# 28Pins_Schematic.net
KiCad netlist of a schematic drawn in Altium Designer
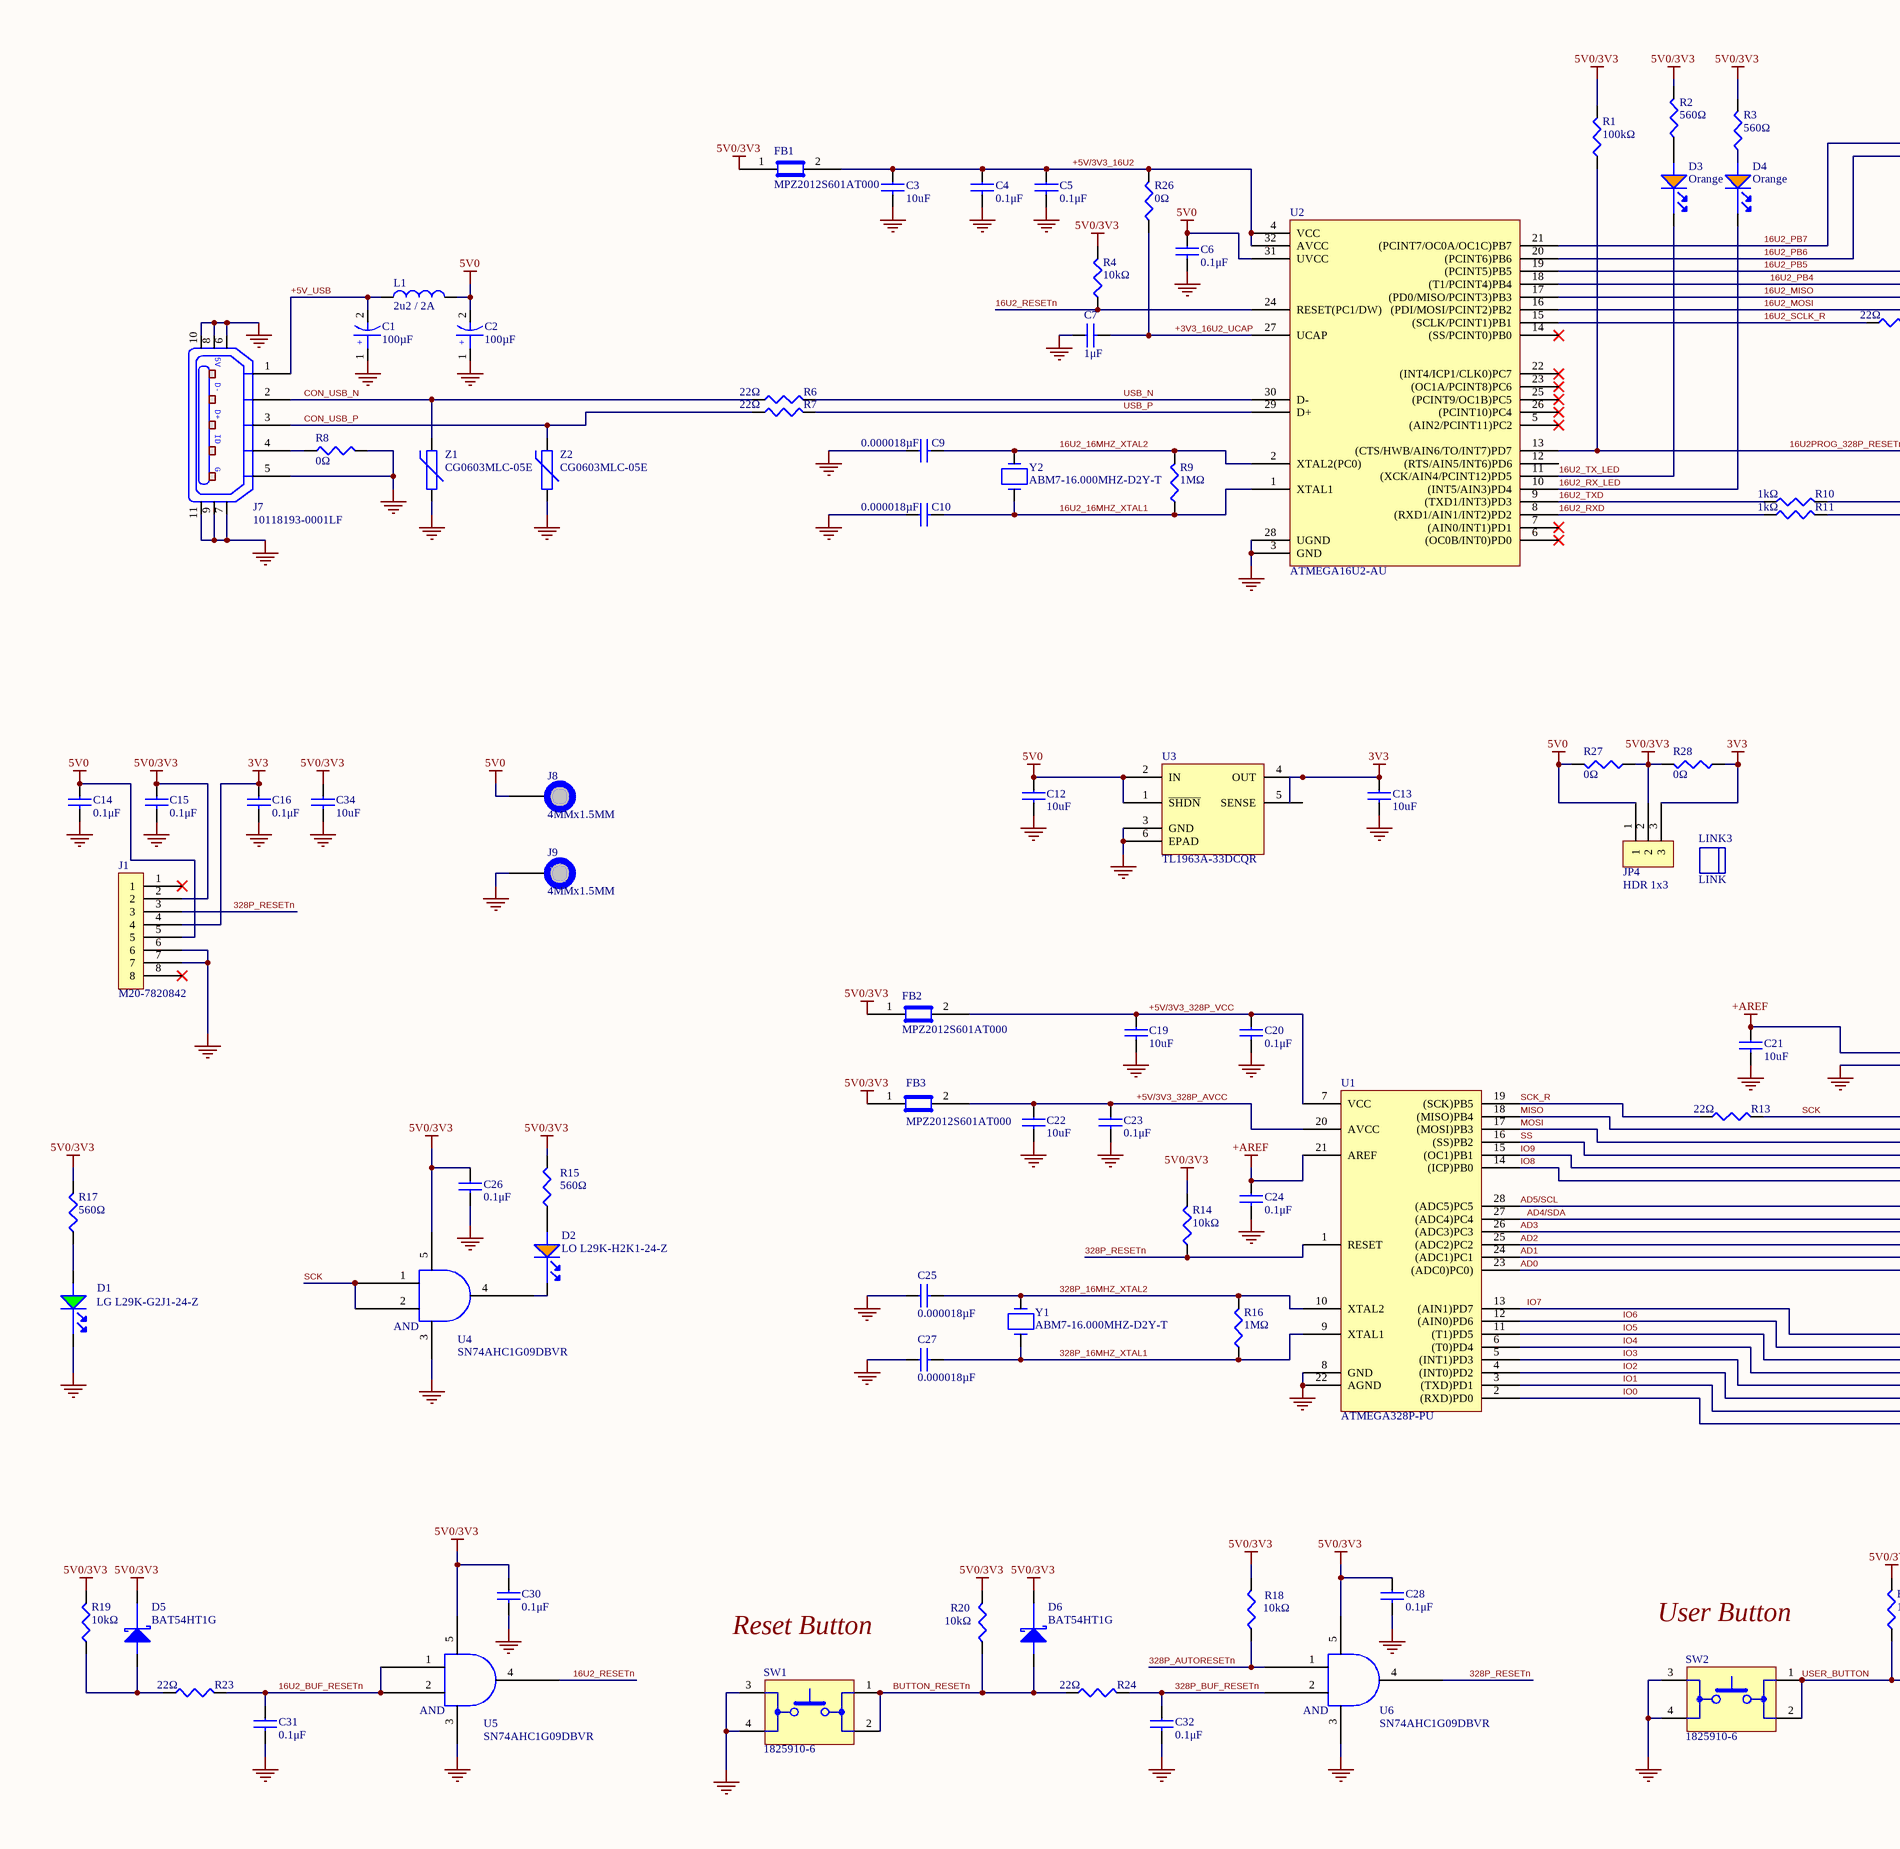
[diagram p0: 28Pins_Schematic.SchDoc, left]
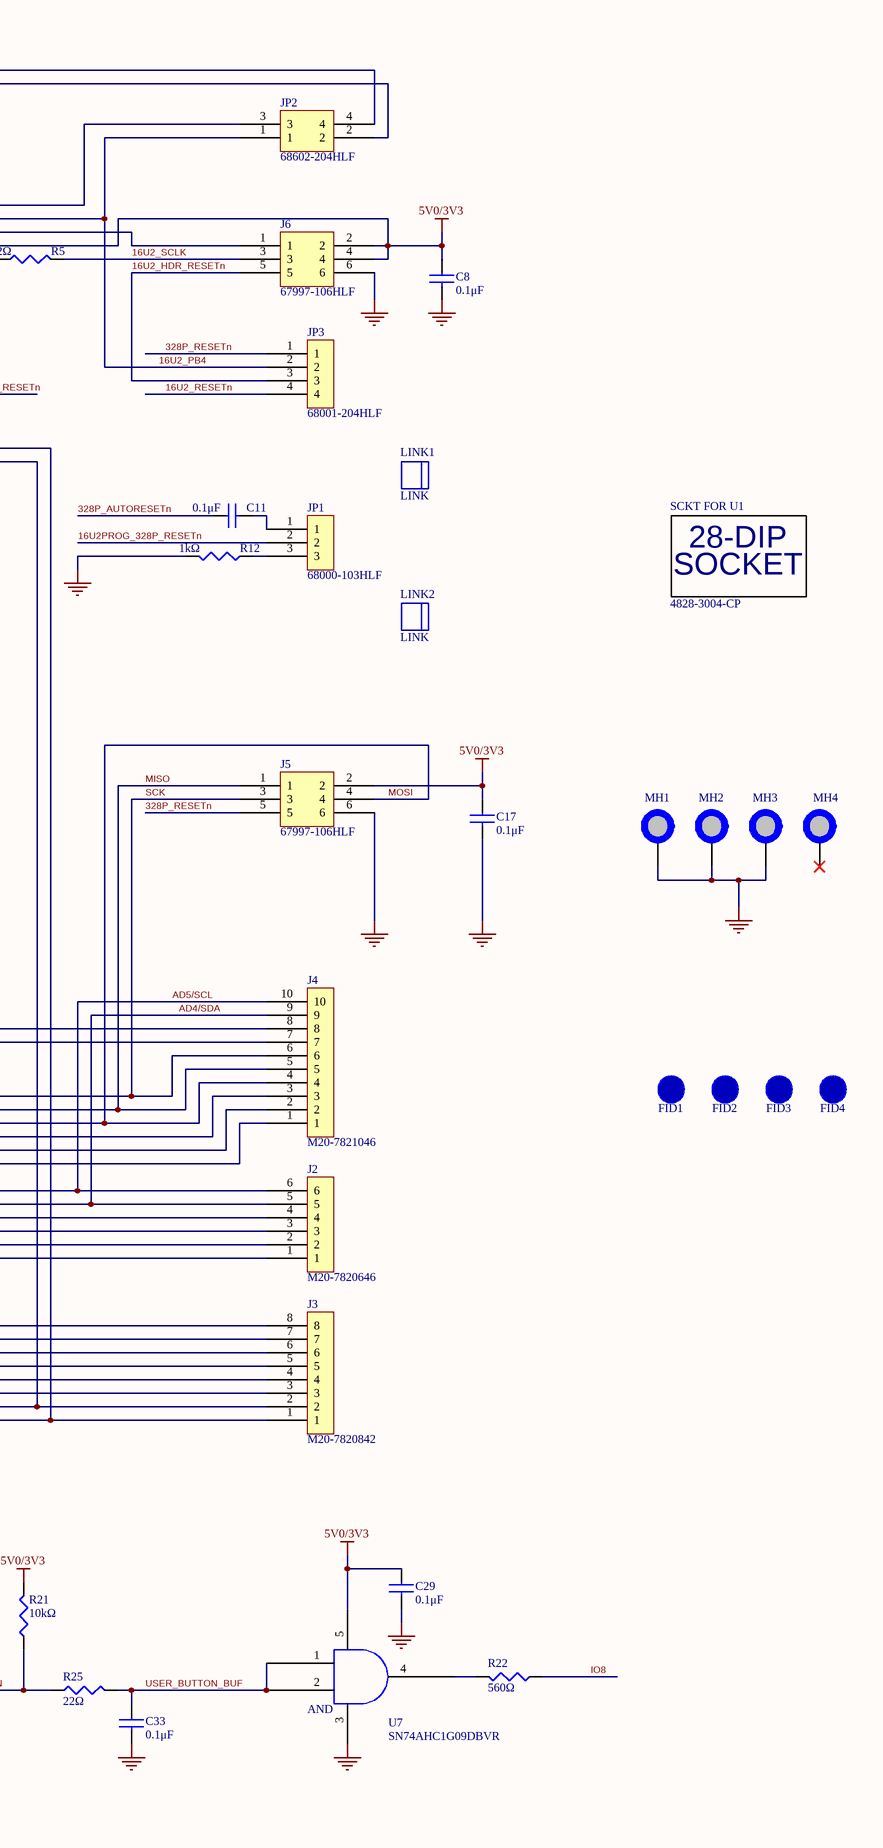
[diagram p1: 28Pins_Schematic.SchDoc, right]

(export (version "E")
  (design (tool "Eeschema 10.0.6"))
  (components
    (comp (ref "C1")
      (value "100µF")
      (footprint "C_ALU_C_SIZE")
      (description "CAP ALUM 100UF 10V 20% SMD")
      (fields
        (field (name "MANUFACTURER") "Panasonic Electronic Components")
        (field (name "MANUFACTURER PART NUMBER") "EEE-1AA101WR")
        (field (name ".CREATOR") "MM")
        (field (name ".CHECKED PCB") "RF")
        (field (name ".CHECKED SCH") "RF")
      )
      (libsource (lib "28Pins_Project_V1I1_PCB") (part "EEE-1AA101WR"))
    )
    (comp (ref "C2")
      (value "100µF")
      (footprint "C_ALU_C_SIZE")
      (description "CAP ALUM 100UF 10V 20% SMD")
      (fields
        (field (name "MANUFACTURER") "Panasonic Electronic Components")
        (field (name "MANUFACTURER PART NUMBER") "EEE-1AA101WR")
        (field (name ".CREATOR") "MM")
        (field (name ".CHECKED PCB") "RF")
        (field (name ".CHECKED SCH") "RF")
      )
      (libsource (lib "28Pins_Project_V1I1_PCB") (part "EEE-1AA101WR"))
    )
    (comp (ref "C3")
      (value "10uF")
      (footprint "C0805")
      (description "CAP CER 10UF 16V 20% X5R 0805")
      (fields
        (field (name "MANUFACTURER") "TDK Corporation")
        (field (name "MANUFACTURER PART NUMBER") "C2012X5R1C106M/1.25")
      )
      (libsource (lib "28Pins_Project_V1I1_PCB") (part "C2012X5R1C106M"))
    )
    (comp (ref "C4")
      (value "0.1μF")
      (footprint "C0805")
      (description "CAP CER 0.1UF 50V 10% X7R 0805")
      (fields
        (field (name "MANUFACTURER") "TDK Corporation")
        (field (name "MANUFACTURER PART NUMBER") "C2012X7R1H104K085AA")
        (field (name ".CREATOR") "MM")
        (field (name ".CHECKED PCB") "RF")
        (field (name ".CHECKED SCH") "RF")
      )
      (libsource (lib "28Pins_Project_V1I1_PCB") (part "C2012X7R1H104K085AA"))
    )
    (comp (ref "C5")
      (value "0.1μF")
      (footprint "C0805")
      (description "CAP CER 0.1UF 50V 10% X7R 0805")
      (fields
        (field (name "MANUFACTURER") "TDK Corporation")
        (field (name "MANUFACTURER PART NUMBER") "C2012X7R1H104K085AA")
        (field (name ".CREATOR") "MM")
        (field (name ".CHECKED PCB") "RF")
        (field (name ".CHECKED SCH") "RF")
      )
      (libsource (lib "28Pins_Project_V1I1_PCB") (part "C2012X7R1H104K085AA"))
    )
    (comp (ref "C6")
      (value "0.1μF")
      (footprint "C0805")
      (description "CAP CER 0.1UF 50V 10% X7R 0805")
      (fields
        (field (name "MANUFACTURER") "TDK Corporation")
        (field (name "MANUFACTURER PART NUMBER") "C2012X7R1H104K085AA")
        (field (name ".CREATOR") "MM")
        (field (name ".CHECKED PCB") "RF")
        (field (name ".CHECKED SCH") "RF")
      )
      (libsource (lib "28Pins_Project_V1I1_PCB") (part "C2012X7R1H104K085AA"))
    )
    (comp (ref "C7")
      (value "1μF")
      (footprint "C0805")
      (description "CAP CER 1UF 25V 10% X5R 0805")
      (fields
        (field (name "MANUFACTURER") "TDK Corporation")
        (field (name "MANUFACTURER PART NUMBER") "C2012X5R1E105K125AA")
        (field (name ".CREATOR") "MM")
        (field (name ".CHECKED PCB") "RF")
        (field (name ".CHECKED SCH") "RF")
      )
      (libsource (lib "28Pins_Project_V1I1_PCB") (part "C2012X5R1E105K125AA"))
    )
    (comp (ref "C8")
      (value "0.1μF")
      (footprint "C0805")
      (description "CAP CER 0.1UF 50V 10% X7R 0805")
      (fields
        (field (name "MANUFACTURER") "TDK Corporation")
        (field (name "MANUFACTURER PART NUMBER") "C2012X7R1H104K085AA")
        (field (name ".CREATOR") "MM")
        (field (name ".CHECKED PCB") "RF")
        (field (name ".CHECKED SCH") "RF")
      )
      (libsource (lib "28Pins_Project_V1I1_PCB") (part "C2012X7R1H104K085AA"))
    )
    (comp (ref "C9")
      (value "0.000018µF")
      (footprint "C0805")
      (description "CAP CER 18PF 50V 5% NP0 0805")
      (fields
        (field (name "MANUFACTURER") "Kemet")
        (field (name "MANUFACTURER PART NUMBER") "C0805C180J5GACTU")
        (field (name ".CREATOR") "MM")
        (field (name ".CHECKED PCB") "RF")
        (field (name ".CHECKED SCH") "RF")
      )
      (libsource (lib "28Pins_Project_V1I1_PCB") (part "C0805C180J5GACTU"))
    )
    (comp (ref "C10")
      (value "0.000018µF")
      (footprint "C0805")
      (description "CAP CER 18PF 50V 5% NP0 0805")
      (fields
        (field (name "MANUFACTURER") "Kemet")
        (field (name "MANUFACTURER PART NUMBER") "C0805C180J5GACTU")
        (field (name ".CREATOR") "MM")
        (field (name ".CHECKED PCB") "RF")
        (field (name ".CHECKED SCH") "RF")
      )
      (libsource (lib "28Pins_Project_V1I1_PCB") (part "C0805C180J5GACTU"))
    )
    (comp (ref "C11")
      (value "0.1μF")
      (footprint "C0805")
      (description "CAP CER 0.1UF 50V 10% X7R 0805")
      (fields
        (field (name "MANUFACTURER") "TDK Corporation")
        (field (name "MANUFACTURER PART NUMBER") "C2012X7R1H104K085AA")
        (field (name ".CREATOR") "MM")
        (field (name ".CHECKED PCB") "RF")
        (field (name ".CHECKED SCH") "RF")
      )
      (libsource (lib "28Pins_Project_V1I1_PCB") (part "C2012X7R1H104K085AA"))
    )
    (comp (ref "C12")
      (value "10uF")
      (footprint "C0805")
      (description "CAP CER 10UF 16V 20% X5R 0805")
      (fields
        (field (name "MANUFACTURER") "TDK Corporation")
        (field (name "MANUFACTURER PART NUMBER") "C2012X5R1C106M/1.25")
      )
      (libsource (lib "28Pins_Project_V1I1_PCB") (part "C2012X5R1C106M"))
    )
    (comp (ref "C13")
      (value "10uF")
      (footprint "C0805")
      (description "CAP CER 10UF 16V 20% X5R 0805")
      (fields
        (field (name "MANUFACTURER") "TDK Corporation")
        (field (name "MANUFACTURER PART NUMBER") "C2012X5R1C106M/1.25")
      )
      (libsource (lib "28Pins_Project_V1I1_PCB") (part "C2012X5R1C106M"))
    )
    (comp (ref "C14")
      (value "0.1μF")
      (footprint "C0805")
      (description "CAP CER 0.1UF 50V 10% X7R 0805")
      (fields
        (field (name "MANUFACTURER") "TDK Corporation")
        (field (name "MANUFACTURER PART NUMBER") "C2012X7R1H104K085AA")
        (field (name ".CREATOR") "MM")
        (field (name ".CHECKED PCB") "RF")
        (field (name ".CHECKED SCH") "RF")
      )
      (libsource (lib "28Pins_Project_V1I1_PCB") (part "C2012X7R1H104K085AA"))
    )
    (comp (ref "C15")
      (value "0.1μF")
      (footprint "C0805")
      (description "CAP CER 0.1UF 50V 10% X7R 0805")
      (fields
        (field (name "MANUFACTURER") "TDK Corporation")
        (field (name "MANUFACTURER PART NUMBER") "C2012X7R1H104K085AA")
        (field (name ".CREATOR") "MM")
        (field (name ".CHECKED PCB") "RF")
        (field (name ".CHECKED SCH") "RF")
      )
      (libsource (lib "28Pins_Project_V1I1_PCB") (part "C2012X7R1H104K085AA"))
    )
    (comp (ref "C16")
      (value "0.1μF")
      (footprint "C0805")
      (description "CAP CER 0.1UF 50V 10% X7R 0805")
      (fields
        (field (name "MANUFACTURER") "TDK Corporation")
        (field (name "MANUFACTURER PART NUMBER") "C2012X7R1H104K085AA")
        (field (name ".CREATOR") "MM")
        (field (name ".CHECKED PCB") "RF")
        (field (name ".CHECKED SCH") "RF")
      )
      (libsource (lib "28Pins_Project_V1I1_PCB") (part "C2012X7R1H104K085AA"))
    )
    (comp (ref "C17")
      (value "0.1μF")
      (footprint "C0805")
      (description "CAP CER 0.1UF 50V 10% X7R 0805")
      (fields
        (field (name "MANUFACTURER") "TDK Corporation")
        (field (name "MANUFACTURER PART NUMBER") "C2012X7R1H104K085AA")
        (field (name ".CREATOR") "MM")
        (field (name ".CHECKED PCB") "RF")
        (field (name ".CHECKED SCH") "RF")
      )
      (libsource (lib "28Pins_Project_V1I1_PCB") (part "C2012X7R1H104K085AA"))
    )
    (comp (ref "C19")
      (value "10uF")
      (footprint "C0805")
      (description "CAP CER 10UF 16V 20% X5R 0805")
      (fields
        (field (name "MANUFACTURER") "TDK Corporation")
        (field (name "MANUFACTURER PART NUMBER") "C2012X5R1C106M/1.25")
      )
      (libsource (lib "28Pins_Project_V1I1_PCB") (part "C2012X5R1C106M"))
    )
    (comp (ref "C20")
      (value "0.1μF")
      (footprint "C0805")
      (description "CAP CER 0.1UF 50V 10% X7R 0805")
      (fields
        (field (name "MANUFACTURER") "TDK Corporation")
        (field (name "MANUFACTURER PART NUMBER") "C2012X7R1H104K085AA")
        (field (name ".CREATOR") "MM")
        (field (name ".CHECKED PCB") "RF")
        (field (name ".CHECKED SCH") "RF")
      )
      (libsource (lib "28Pins_Project_V1I1_PCB") (part "C2012X7R1H104K085AA"))
    )
    (comp (ref "C21")
      (value "10uF")
      (footprint "C0805")
      (description "CAP CER 10UF 16V 20% X5R 0805")
      (fields
        (field (name "MANUFACTURER") "TDK Corporation")
        (field (name "MANUFACTURER PART NUMBER") "C2012X5R1C106M/1.25")
      )
      (libsource (lib "28Pins_Project_V1I1_PCB") (part "C2012X5R1C106M"))
    )
    (comp (ref "C22")
      (value "10uF")
      (footprint "C0805")
      (description "CAP CER 10UF 16V 20% X5R 0805")
      (fields
        (field (name "MANUFACTURER") "TDK Corporation")
        (field (name "MANUFACTURER PART NUMBER") "C2012X5R1C106M/1.25")
      )
      (libsource (lib "28Pins_Project_V1I1_PCB") (part "C2012X5R1C106M"))
    )
    (comp (ref "C23")
      (value "0.1μF")
      (footprint "C0805")
      (description "CAP CER 0.1UF 50V 10% X7R 0805")
      (fields
        (field (name "MANUFACTURER") "TDK Corporation")
        (field (name "MANUFACTURER PART NUMBER") "C2012X7R1H104K085AA")
        (field (name ".CREATOR") "MM")
        (field (name ".CHECKED PCB") "RF")
        (field (name ".CHECKED SCH") "RF")
      )
      (libsource (lib "28Pins_Project_V1I1_PCB") (part "C2012X7R1H104K085AA"))
    )
    (comp (ref "C24")
      (value "0.1μF")
      (footprint "C0805")
      (description "CAP CER 0.1UF 50V 10% X7R 0805")
      (fields
        (field (name "MANUFACTURER") "TDK Corporation")
        (field (name "MANUFACTURER PART NUMBER") "C2012X7R1H104K085AA")
        (field (name ".CREATOR") "MM")
        (field (name ".CHECKED PCB") "RF")
        (field (name ".CHECKED SCH") "RF")
      )
      (libsource (lib "28Pins_Project_V1I1_PCB") (part "C2012X7R1H104K085AA"))
    )
    (comp (ref "C25")
      (value "0.000018µF")
      (footprint "C0805")
      (description "CAP CER 18PF 50V 5% NP0 0805")
      (fields
        (field (name "MANUFACTURER") "Kemet")
        (field (name "MANUFACTURER PART NUMBER") "C0805C180J5GACTU")
        (field (name ".CREATOR") "MM")
        (field (name ".CHECKED PCB") "RF")
        (field (name ".CHECKED SCH") "RF")
      )
      (libsource (lib "28Pins_Project_V1I1_PCB") (part "C0805C180J5GACTU"))
    )
    (comp (ref "C26")
      (value "0.1μF")
      (footprint "C0805")
      (description "CAP CER 0.1UF 50V 10% X7R 0805")
      (fields
        (field (name "MANUFACTURER") "TDK Corporation")
        (field (name "MANUFACTURER PART NUMBER") "C2012X7R1H104K085AA")
        (field (name ".CREATOR") "MM")
        (field (name ".CHECKED PCB") "RF")
        (field (name ".CHECKED SCH") "RF")
      )
      (libsource (lib "28Pins_Project_V1I1_PCB") (part "C2012X7R1H104K085AA"))
    )
    (comp (ref "C27")
      (value "0.000018µF")
      (footprint "C0805")
      (description "CAP CER 18PF 50V 5% NP0 0805")
      (fields
        (field (name "MANUFACTURER") "Kemet")
        (field (name "MANUFACTURER PART NUMBER") "C0805C180J5GACTU")
        (field (name ".CREATOR") "MM")
        (field (name ".CHECKED PCB") "RF")
        (field (name ".CHECKED SCH") "RF")
      )
      (libsource (lib "28Pins_Project_V1I1_PCB") (part "C0805C180J5GACTU"))
    )
    (comp (ref "C28")
      (value "0.1μF")
      (footprint "C0805")
      (description "CAP CER 0.1UF 50V 10% X7R 0805")
      (fields
        (field (name "MANUFACTURER") "TDK Corporation")
        (field (name "MANUFACTURER PART NUMBER") "C2012X7R1H104K085AA")
        (field (name ".CREATOR") "MM")
        (field (name ".CHECKED PCB") "RF")
        (field (name ".CHECKED SCH") "RF")
      )
      (libsource (lib "28Pins_Project_V1I1_PCB") (part "C2012X7R1H104K085AA"))
    )
    (comp (ref "C29")
      (value "0.1μF")
      (footprint "C0805")
      (description "CAP CER 0.1UF 50V 10% X7R 0805")
      (fields
        (field (name "MANUFACTURER") "TDK Corporation")
        (field (name "MANUFACTURER PART NUMBER") "C2012X7R1H104K085AA")
        (field (name ".CREATOR") "MM")
        (field (name ".CHECKED PCB") "RF")
        (field (name ".CHECKED SCH") "RF")
      )
      (libsource (lib "28Pins_Project_V1I1_PCB") (part "C2012X7R1H104K085AA"))
    )
    (comp (ref "C30")
      (value "0.1μF")
      (footprint "C0805")
      (description "CAP CER 0.1UF 50V 10% X7R 0805")
      (fields
        (field (name "MANUFACTURER") "TDK Corporation")
        (field (name "MANUFACTURER PART NUMBER") "C2012X7R1H104K085AA")
        (field (name ".CREATOR") "MM")
        (field (name ".CHECKED PCB") "RF")
        (field (name ".CHECKED SCH") "RF")
      )
      (libsource (lib "28Pins_Project_V1I1_PCB") (part "C2012X7R1H104K085AA"))
    )
    (comp (ref "C31")
      (value "0.1μF")
      (footprint "C0805")
      (description "CAP CER 0.1UF 50V 10% X7R 0805")
      (fields
        (field (name "MANUFACTURER") "TDK Corporation")
        (field (name "MANUFACTURER PART NUMBER") "C2012X7R1H104K085AA")
        (field (name ".CREATOR") "MM")
        (field (name ".CHECKED PCB") "RF")
        (field (name ".CHECKED SCH") "RF")
      )
      (libsource (lib "28Pins_Project_V1I1_PCB") (part "C2012X7R1H104K085AA"))
    )
    (comp (ref "C32")
      (value "0.1μF")
      (footprint "C0805")
      (description "CAP CER 0.1UF 50V 10% X7R 0805")
      (fields
        (field (name "MANUFACTURER") "TDK Corporation")
        (field (name "MANUFACTURER PART NUMBER") "C2012X7R1H104K085AA")
        (field (name ".CREATOR") "MM")
        (field (name ".CHECKED PCB") "RF")
        (field (name ".CHECKED SCH") "RF")
      )
      (libsource (lib "28Pins_Project_V1I1_PCB") (part "C2012X7R1H104K085AA"))
    )
    (comp (ref "C33")
      (value "0.1μF")
      (footprint "C0805")
      (description "CAP CER 0.1UF 50V 10% X7R 0805")
      (fields
        (field (name "MANUFACTURER") "TDK Corporation")
        (field (name "MANUFACTURER PART NUMBER") "C2012X7R1H104K085AA")
        (field (name ".CREATOR") "MM")
        (field (name ".CHECKED PCB") "RF")
        (field (name ".CHECKED SCH") "RF")
      )
      (libsource (lib "28Pins_Project_V1I1_PCB") (part "C2012X7R1H104K085AA"))
    )
    (comp (ref "C34")
      (value "10uF")
      (footprint "C0805")
      (description "CAP CER 10UF 16V 20% X5R 0805")
      (fields
        (field (name "MANUFACTURER") "TDK Corporation")
        (field (name "MANUFACTURER PART NUMBER") "C2012X5R1C106M/1.25")
      )
      (libsource (lib "28Pins_Project_V1I1_PCB") (part "C2012X5R1C106M"))
    )
    (comp (ref "D1")
      (value "LG L29K-G2J1-24-Z")
      (footprint "LED_0603")
      (description "LED SMARTLED GREEN 570NM 0603")
      (fields (field (name "MANUFACTURER") "OSRAM Opto Semiconductors Inc"))
      (libsource (lib "28Pins_Project_V1I1_PCB") (part "LG L29K-G2J1-24-Z"))
    )
    (comp (ref "D2")
      (value "LO L29K-H2K1-24-Z")
      (footprint "LED_0603")
      (description "LED SMARTLED ORANGE 606NM 0603")
      (fields (field (name "MANUFACTURER") "OSRAM Opto Semiconductors Inc"))
      (libsource (lib "28Pins_Project_V1I1_PCB") (part "LO L29K-H2K1-24-Z"))
    )
    (comp (ref "D3")
      (value "Orange")
      (footprint "LED_0603")
      (description "LED SMARTLED ORANGE 606NM 0603")
      (fields
        (field (name "MANUFACTURER") "OSRAM Opto Semiconductors Inc")
        (field (name "MANUFACTURER PART NUMBER") "LO L29K-H2K1-24-Z")
      )
      (libsource (lib "28Pins_Project_V1I1_PCB") (part "LO L29K-H2K1-24-Z"))
    )
    (comp (ref "D4")
      (value "Orange")
      (footprint "LED_0603")
      (description "LED SMARTLED ORANGE 606NM 0603")
      (fields
        (field (name "MANUFACTURER") "OSRAM Opto Semiconductors Inc")
        (field (name "MANUFACTURER PART NUMBER") "LO L29K-H2K1-24-Z")
      )
      (libsource (lib "28Pins_Project_V1I1_PCB") (part "LO L29K-H2K1-24-Z"))
    )
    (comp (ref "D5")
      (value "BAT54HT1G")
      (footprint "SOD323")
      (description "DIODE SCHOTTKY 30V 0.2A SOD323")
      (fields (field (name "MANUFACTURER") "Fairchild Semiconductor") (field (name ".CREATOR") "MM"))
      (libsource (lib "28Pins_Project_V1I1_PCB") (part "BAT54HT1G"))
    )
    (comp (ref "D6")
      (value "BAT54HT1G")
      (footprint "SOD323")
      (description "DIODE SCHOTTKY 30V 0.2A SOD323")
      (fields (field (name "MANUFACTURER") "Fairchild Semiconductor") (field (name ".CREATOR") "MM"))
      (libsource (lib "28Pins_Project_V1I1_PCB") (part "BAT54HT1G"))
    )
    (comp (ref "FB1")
      (value "MPZ2012S601AT000")
      (footprint "C0805")
      (description "FERRITE CHIP BEAD 600 OHM SMD")
      (fields
        (field (name "MANUFACTURER") "TDK Corporation")
        (field (name ".CREATOR") "MM")
        (field (name ".CHECKED PCB") "RF")
        (field (name ".CHECKED SCH") "RF")
      )
      (libsource (lib "28Pins_Project_V1I1_PCB") (part "MPZ2012S601AT000"))
    )
    (comp (ref "FB2")
      (value "MPZ2012S601AT000")
      (footprint "C0805")
      (description "FERRITE CHIP BEAD 600 OHM SMD")
      (fields
        (field (name "MANUFACTURER") "TDK Corporation")
        (field (name ".CREATOR") "MM")
        (field (name ".CHECKED PCB") "RF")
        (field (name ".CHECKED SCH") "RF")
      )
      (libsource (lib "28Pins_Project_V1I1_PCB") (part "MPZ2012S601AT000"))
    )
    (comp (ref "FB3")
      (value "MPZ2012S601AT000")
      (footprint "C0805")
      (description "FERRITE CHIP BEAD 600 OHM SMD")
      (fields
        (field (name "MANUFACTURER") "TDK Corporation")
        (field (name ".CREATOR") "MM")
        (field (name ".CHECKED PCB") "RF")
        (field (name ".CHECKED SCH") "RF")
      )
      (libsource (lib "28Pins_Project_V1I1_PCB") (part "MPZ2012S601AT000"))
    )
    (comp (ref "FID1")
      (value "FID_1MMC")
      (footprint "FID_40X120D")
      (description "Fiducial 40mil Diameter, 120mil Mask")
      (libsource (lib "28Pins_Project_V1I1_PCB") (part "FID_1MMC"))
    )
    (comp (ref "FID2")
      (value "FID_1MMC")
      (footprint "FID_40X120D")
      (description "Fiducial 40mil Diameter, 120mil Mask")
      (libsource (lib "28Pins_Project_V1I1_PCB") (part "FID_1MMC"))
    )
    (comp (ref "FID3")
      (value "FID_1MMC")
      (footprint "FID_40X120D")
      (description "Fiducial 40mil Diameter, 120mil Mask")
      (libsource (lib "28Pins_Project_V1I1_PCB") (part "FID_1MMC"))
    )
    (comp (ref "FID4")
      (value "FID_1MMC")
      (footprint "FID_40X120D")
      (description "Fiducial 40mil Diameter, 120mil Mask")
      (libsource (lib "28Pins_Project_V1I1_PCB") (part "FID_1MMC"))
    )
    (comp (ref "J1")
      (value "M20-7820842")
      (footprint "Hdr_Female_1x8_2.54mm")
      (description "08-WAY SIL VERT SOCKET L/FREE")
      (fields
        (field (name "MANUFACTURER") "Harwin Inc")
        (field (name ".CREATOR") "MM")
        (field (name ".CHECKED PCB") "RF")
        (field (name ".CHECKED SCH") "RF")
      )
      (libsource (lib "") (part "M20-7820842_1"))
    )
    (comp (ref "J2")
      (value "M20-7820646")
      (footprint "Hdr_Female_1x6_2.54mm")
      (description "06-WAY SIL VERT SOCKET L/FREE")
      (fields
        (field (name "MANUFACTURER") "Harwin Inc")
        (field (name ".CHECKED PCB") "MM")
        (field (name ".CHECKED SCH") "MM")
        (field (name ".CREATOR") "MM")
      )
      (libsource (lib "28Pins_Project_V1I1_PCB") (part "M20-7820646"))
    )
    (comp (ref "J3")
      (value "M20-7820842")
      (footprint "Hdr_Female_1x8_2.54mm")
      (description "08-WAY SIL VERT SOCKET L/FREE")
      (fields
        (field (name "MANUFACTURER") "Harwin Inc")
        (field (name ".CREATOR") "MM")
        (field (name ".CHECKED PCB") "RF")
        (field (name ".CHECKED SCH") "RF")
      )
      (libsource (lib "28Pins_Project_V1I1_PCB") (part "M20-7820842"))
    )
    (comp (ref "J4")
      (value "M20-7821046")
      (footprint "Hdr_Female_1x10_2.54mm")
      (description "10-WAY SIL VERT SOCKET L/FREE")
      (fields
        (field (name "MANUFACTURER") "Harwin Inc")
        (field (name ".CREATOR") "MM")
        (field (name ".CHECKED PCB") "RF")
        (field (name ".CHECKED SCH") "RF")
      )
      (libsource (lib "28Pins_Project_V1I1_PCB") (part "M20-7821046"))
    )
    (comp (ref "J5")
      (value "67997-106HLF")
      (footprint "HDR_2x3_2.54MM")
      (description "CONN HEADER 6POS .100 STR 30AU")
      (fields
        (field (name "MANUFACTURER") "FCI")
        (field (name ".CREATOR") "MM")
        (field (name ".CHECKED PCB") "RF")
        (field (name ".CHECKED SCH") "RF")
      )
      (libsource (lib "28Pins_Project_V1I1_PCB") (part "67997-106HLF"))
    )
    (comp (ref "J6")
      (value "67997-106HLF")
      (footprint "HDR_2x3_2.54MM")
      (description "CONN HEADER 6POS .100 STR 30AU")
      (fields
        (field (name "MANUFACTURER") "FCI")
        (field (name ".CREATOR") "MM")
        (field (name ".CHECKED PCB") "RF")
        (field (name ".CHECKED SCH") "RF")
      )
      (libsource (lib "28Pins_Project_V1I1_PCB") (part "67997-106HLF"))
    )
    (comp (ref "J7")
      (value "10118193-0001LF")
      (footprint "10118193")
      (description "CONN USB MICRO B RECPT SMT R/A")
      (fields
        (field (name "MANUFACTURER") "FCI")
        (field (name ".CREATOR") "MM")
        (field (name ".CHECKED PCB") "RF")
        (field (name ".CHECKED SCH") "MM")
      )
      (libsource (lib "28Pins_Project_V1I1_PCB") (part "10118193-0001LF"))
    )
    (comp (ref "J8")
      (value "4MMx1.5MM")
      (footprint "PAD_WITH_HOLE_4MMx1.5MM")
      (description "Pad with a hole 4mm x 1.5mm")
      (libsource (lib "28Pins_Project_V1I1_PCB") (part "PAD_WITH_HOLE_4MMx1.5MM"))
    )
    (comp (ref "J9")
      (value "4MMx1.5MM")
      (footprint "PAD_WITH_HOLE_4MMx1.5MM")
      (description "Pad with a hole 4mm x 1.5mm")
      (libsource (lib "28Pins_Project_V1I1_PCB") (part "PAD_WITH_HOLE_4MMx1.5MM"))
    )
    (comp (ref "JP1")
      (value "68000-103HLF")
      (footprint "Hdr_1x3_2.54mm")
      (description "BERGSTIK II .100\" SR STRAIGHT")
      (fields (field (name "MANUFACTURER") "FCI") (field (name ".CREATOR") "MM"))
      (libsource (lib "28Pins_Project_V1I1_PCB") (part "68000-103HLF"))
    )
    (comp (ref "JP2")
      (value "68602-204HLF")
      (footprint "HDR_2x2_2.54MM")
      (description "CONN HEADER 4POS .100 STR 15AU")
      (fields
        (field (name "MANUFACTURER") "FCI")
        (field (name ".CREATOR") "MM")
        (field (name ".CHECKED PCB") "RF")
        (field (name ".CHECKED SCH") "RF")
      )
      (libsource (lib "28Pins_Project_V1I1_PCB") (part "68602-204HLF"))
    )
    (comp (ref "JP3")
      (value "68001-204HLF")
      (footprint "HDR_1x4_2.54MM")
      (description "CONN HEADER 4POS .100 STR 15AU")
      (fields
        (field (name "MANUFACTURER") "FCI")
        (field (name ".CHECKED PCB") "RF")
        (field (name ".CHECKED SCH") "RF")
      )
      (libsource (lib "28Pins_Project_V1I1_PCB") (part "68001-204HLF"))
    )
    (comp (ref "JP4")
      (value "HDR 1x3")
      (footprint "Hdr_1x3_2.54mm")
      (description "BERGSTIK II .100\" SR STRAIGHT")
      (fields
        (field (name "MANUFACTURER") "FCI")
        (field (name "MANUFACTURER PART NUMBER") "68000-103HLF")
        (field (name ".CREATOR") "MM")
      )
      (libsource (lib "") (part "68000-103HLF_1"))
    )
    (comp (ref "L1")
      (value "2u2 / 2A")
      (footprint "C1210_IND")
      (description "FIXED IND 2.2UH 2A 80 MOHM SMD")
      (fields
        (field (name "MANUFACTURER") "Kemet")
        (field (name "MANUFACTURER PART NUMBER") "L1210R2R2MDWIT")
        (field (name ".CREATOR") "MM")
        (field (name ".CHECKED PCB") "RF")
        (field (name ".CHECKED SCH") "RF")
      )
      (libsource (lib "28Pins_Project_V1I1_PCB") (part "L1210R2R2MDWIT"))
    )
    (comp (ref "LINK1")
      (value "LINK")
      (description "CONN JUMPER SHORTING .100\" GOLD")
      (fields
        (field (name "MANUFACTURER") "Sullins Connector Solutions")
        (field (name "MANUFACTURER PART NUMBER") "QPC02SXGN-RC")
      )
      (libsource (lib "28Pins_Project_V1I1_PCB") (part "QPC02SXGN-RC"))
    )
    (comp (ref "LINK2")
      (value "LINK")
      (description "CONN JUMPER SHORTING .100\" GOLD")
      (fields
        (field (name "MANUFACTURER") "Sullins Connector Solutions")
        (field (name "MANUFACTURER PART NUMBER") "QPC02SXGN-RC")
      )
      (libsource (lib "28Pins_Project_V1I1_PCB") (part "QPC02SXGN-RC"))
    )
    (comp (ref "LINK3")
      (value "LINK")
      (description "CONN JUMPER SHORTING .100\" GOLD")
      (fields
        (field (name "MANUFACTURER") "Sullins Connector Solutions")
        (field (name "MANUFACTURER PART NUMBER") "QPC02SXGN-RC")
      )
      (libsource (lib "28Pins_Project_V1I1_PCB") (part "QPC02SXGN-RC"))
    )
    (comp (ref "MH1")
      (value "MH_7.4MMC_3.2MMD")
      (footprint "MH_7.4MMD_3.2MMD")
      (description "Mounting Hole 7.4mm Diameter, 3.2mm Drill")
      (fields (field (name ".CREATOR") "MM"))
      (libsource (lib "28Pins_Project_V1I1_PCB") (part "MH_7.4MMC_3.2MMD"))
    )
    (comp (ref "MH2")
      (value "MH_7.4MMC_3.2MMD")
      (footprint "MH_7.4MMD_3.2MMD")
      (description "Mounting Hole 7.4mm Diameter, 3.2mm Drill")
      (fields (field (name ".CREATOR") "MM"))
      (libsource (lib "28Pins_Project_V1I1_PCB") (part "MH_7.4MMC_3.2MMD"))
    )
    (comp (ref "MH3")
      (value "MH_7.4MMC_3.2MMD")
      (footprint "MH_7.4MMD_3.2MMD")
      (description "Mounting Hole 7.4mm Diameter, 3.2mm Drill")
      (fields (field (name ".CREATOR") "MM"))
      (libsource (lib "28Pins_Project_V1I1_PCB") (part "MH_7.4MMC_3.2MMD"))
    )
    (comp (ref "MH4")
      (value "MH_7.4MMNC_3.2MMD")
      (footprint "MH_7.4MMD_3.2MMD_NON_COPPER_NPTH")
      (description "Mounting Hole 7.4mm Diameter (Non Copper), 3.2mm Drill NPTH")
      (libsource (lib "28Pins_Project_V1I1_PCB") (part "MH_7.4MMNC_3.2MMD"))
    )
    (comp (ref "R1")
      (value "100kΩ")
      (footprint "R0805")
      (description "RES SMD 100K OHM 1% 1/8W 0805")
      (fields
        (field (name "MANUFACTURER") "Yageo")
        (field (name "MANUFACTURER PART NUMBER") "RC0805FR-07100KL")
        (field (name ".CREATOR") "MM")
        (field (name ".CHECKED PCB") "RF")
        (field (name ".CHECKED SCH") "RF")
      )
      (libsource (lib "28Pins_Project_V1I1_PCB") (part "RC0805FR-07100KL"))
    )
    (comp (ref "R2")
      (value "560Ω")
      (footprint "R0805")
      (description "RES SMD 560 OHM 1% 1/8W 0805")
      (fields
        (field (name "MANUFACTURER") "Yageo")
        (field (name "MANUFACTURER PART NUMBER") "RC0805FR-07560RL")
        (field (name ".CREATOR") "MM")
        (field (name ".CHECKED PCB") "RF")
        (field (name ".CHECKED SCH") "RF")
      )
      (libsource (lib "28Pins_Project_V1I1_PCB") (part "RC0805FR-07560RL"))
    )
    (comp (ref "R3")
      (value "560Ω")
      (footprint "R0805")
      (description "RES SMD 560 OHM 1% 1/8W 0805")
      (fields
        (field (name "MANUFACTURER") "Yageo")
        (field (name "MANUFACTURER PART NUMBER") "RC0805FR-07560RL")
        (field (name ".CREATOR") "MM")
        (field (name ".CHECKED PCB") "RF")
        (field (name ".CHECKED SCH") "RF")
      )
      (libsource (lib "28Pins_Project_V1I1_PCB") (part "RC0805FR-07560RL"))
    )
    (comp (ref "R4")
      (value "10kΩ")
      (footprint "R0805")
      (description "RES SMD 10K OHM 1% 1/8W 0805")
      (fields
        (field (name "MANUFACTURER") "Yageo")
        (field (name "MANUFACTURER PART NUMBER") "RC0805FR-0710KL")
        (field (name ".CREATOR") "MM")
        (field (name ".CHECKED PCB") "RF")
        (field (name ".CHECKED SCH") "RF")
      )
      (libsource (lib "28Pins_Project_V1I1_PCB") (part "RC0805FR-0710KL"))
    )
    (comp (ref "R5")
      (value "22Ω")
      (footprint "R0805")
      (description "RES SMD 22 OHM 1% 1/8W 0805")
      (fields
        (field (name "MANUFACTURER") "Yageo")
        (field (name "MANUFACTURER PART NUMBER") "RC0805FR-0722RL")
        (field (name ".CREATOR") "MM")
        (field (name ".CHECKED PCB") "RF")
        (field (name ".CHECKED SCH") "RF")
      )
      (libsource (lib "28Pins_Project_V1I1_PCB") (part "RC0805FR-0722RL"))
    )
    (comp (ref "R6")
      (value "22Ω")
      (footprint "R0805")
      (description "RES SMD 22 OHM 1% 1/8W 0805")
      (fields
        (field (name "MANUFACTURER") "Yageo")
        (field (name "MANUFACTURER PART NUMBER") "RC0805FR-0722RL")
        (field (name ".CREATOR") "MM")
        (field (name ".CHECKED PCB") "RF")
        (field (name ".CHECKED SCH") "RF")
      )
      (libsource (lib "28Pins_Project_V1I1_PCB") (part "RC0805FR-0722RL"))
    )
    (comp (ref "R7")
      (value "22Ω")
      (footprint "R0805")
      (description "RES SMD 22 OHM 1% 1/8W 0805")
      (fields
        (field (name "MANUFACTURER") "Yageo")
        (field (name "MANUFACTURER PART NUMBER") "RC0805FR-0722RL")
        (field (name ".CREATOR") "MM")
        (field (name ".CHECKED PCB") "RF")
        (field (name ".CHECKED SCH") "RF")
      )
      (libsource (lib "28Pins_Project_V1I1_PCB") (part "RC0805FR-0722RL"))
    )
    (comp (ref "R8")
      (value "0Ω")
      (footprint "R0805")
      (description "RES 0.0 OHM 1/8W 0805 SMD")
      (fields
        (field (name "MANUFACTURER") "Yageo")
        (field (name "MANUFACTURER PART NUMBER") "RC0805JR-070RL")
        (field (name ".CHECKED PCB") "RF")
        (field (name ".CHECKED SCH") "RF")
      )
      (libsource (lib "28Pins_Project_V1I1_PCB") (part "RC0805JR-070RL"))
    )
    (comp (ref "R9")
      (value "1MΩ")
      (footprint "R0805")
      (description "RES SMD 1M OHM 1% 1/8W 0805")
      (fields
        (field (name "MANUFACTURER") "Yageo")
        (field (name "MANUFACTURER PART NUMBER") "RC0805FR-071ML")
        (field (name ".CREATOR") "MM")
        (field (name ".CHECKED PCB") "RF")
        (field (name ".CHECKED SCH") "RF")
      )
      (libsource (lib "28Pins_Project_V1I1_PCB") (part "RC0805FR-071ML"))
    )
    (comp (ref "R10")
      (value "1kΩ")
      (footprint "R0805")
      (description "RES SMD 1K OHM 1% 1/8W 0805")
      (fields
        (field (name "MANUFACTURER") "Yageo")
        (field (name "MANUFACTURER PART NUMBER") "RC0805FR-071KL")
        (field (name ".CREATOR") "MM")
        (field (name ".CHECKED PCB") "RF")
        (field (name ".CHECKED SCH") "RF")
      )
      (libsource (lib "28Pins_Project_V1I1_PCB") (part "RC0805FR-071KL"))
    )
    (comp (ref "R11")
      (value "1kΩ")
      (footprint "R0805")
      (description "RES SMD 1K OHM 1% 1/8W 0805")
      (fields
        (field (name "MANUFACTURER") "Yageo")
        (field (name "MANUFACTURER PART NUMBER") "RC0805FR-071KL")
        (field (name ".CREATOR") "MM")
        (field (name ".CHECKED PCB") "RF")
        (field (name ".CHECKED SCH") "RF")
      )
      (libsource (lib "28Pins_Project_V1I1_PCB") (part "RC0805FR-071KL"))
    )
    (comp (ref "R12")
      (value "1kΩ")
      (footprint "R0805")
      (description "RES SMD 1K OHM 1% 1/8W 0805")
      (fields
        (field (name "MANUFACTURER") "Yageo")
        (field (name "MANUFACTURER PART NUMBER") "RC0805FR-071KL")
        (field (name ".CREATOR") "MM")
        (field (name ".CHECKED PCB") "RF")
        (field (name ".CHECKED SCH") "RF")
      )
      (libsource (lib "28Pins_Project_V1I1_PCB") (part "RC0805FR-071KL"))
    )
    (comp (ref "R13")
      (value "22Ω")
      (footprint "R0805")
      (description "RES SMD 22 OHM 1% 1/8W 0805")
      (fields
        (field (name "MANUFACTURER") "Yageo")
        (field (name "MANUFACTURER PART NUMBER") "RC0805FR-0722RL")
        (field (name ".CREATOR") "MM")
        (field (name ".CHECKED PCB") "RF")
        (field (name ".CHECKED SCH") "RF")
      )
      (libsource (lib "28Pins_Project_V1I1_PCB") (part "RC0805FR-0722RL"))
    )
    (comp (ref "R14")
      (value "10kΩ")
      (footprint "R0805")
      (description "RES SMD 10K OHM 1% 1/8W 0805")
      (fields
        (field (name "MANUFACTURER") "Yageo")
        (field (name "MANUFACTURER PART NUMBER") "RC0805FR-0710KL")
        (field (name ".CREATOR") "MM")
        (field (name ".CHECKED PCB") "RF")
        (field (name ".CHECKED SCH") "RF")
      )
      (libsource (lib "28Pins_Project_V1I1_PCB") (part "RC0805FR-0710KL"))
    )
    (comp (ref "R15")
      (value "560Ω")
      (footprint "R0805")
      (description "RES SMD 560 OHM 1% 1/8W 0805")
      (fields
        (field (name "MANUFACTURER") "Yageo")
        (field (name "MANUFACTURER PART NUMBER") "RC0805FR-07560RL")
        (field (name ".CREATOR") "MM")
        (field (name ".CHECKED PCB") "RF")
        (field (name ".CHECKED SCH") "RF")
      )
      (libsource (lib "28Pins_Project_V1I1_PCB") (part "RC0805FR-07560RL"))
    )
    (comp (ref "R16")
      (value "1MΩ")
      (footprint "R0805")
      (description "RES SMD 1M OHM 1% 1/8W 0805")
      (fields
        (field (name "MANUFACTURER") "Yageo")
        (field (name "MANUFACTURER PART NUMBER") "RC0805FR-071ML")
        (field (name ".CREATOR") "MM")
        (field (name ".CHECKED PCB") "RF")
        (field (name ".CHECKED SCH") "RF")
      )
      (libsource (lib "28Pins_Project_V1I1_PCB") (part "RC0805FR-071ML"))
    )
    (comp (ref "R17")
      (value "560Ω")
      (footprint "R0805")
      (description "RES SMD 560 OHM 1% 1/8W 0805")
      (fields
        (field (name "MANUFACTURER") "Yageo")
        (field (name "MANUFACTURER PART NUMBER") "RC0805FR-07560RL")
        (field (name ".CREATOR") "MM")
        (field (name ".CHECKED PCB") "RF")
        (field (name ".CHECKED SCH") "RF")
      )
      (libsource (lib "28Pins_Project_V1I1_PCB") (part "RC0805FR-07560RL"))
    )
    (comp (ref "R18")
      (value "10kΩ")
      (footprint "R0805")
      (description "RES SMD 10K OHM 1% 1/8W 0805")
      (fields
        (field (name "MANUFACTURER") "Yageo")
        (field (name "MANUFACTURER PART NUMBER") "RC0805FR-0710KL")
        (field (name ".CREATOR") "MM")
        (field (name ".CHECKED PCB") "RF")
        (field (name ".CHECKED SCH") "RF")
      )
      (libsource (lib "28Pins_Project_V1I1_PCB") (part "RC0805FR-0710KL"))
    )
    (comp (ref "R19")
      (value "10kΩ")
      (footprint "R0805")
      (description "RES SMD 10K OHM 1% 1/8W 0805")
      (fields
        (field (name "MANUFACTURER") "Yageo")
        (field (name "MANUFACTURER PART NUMBER") "RC0805FR-0710KL")
        (field (name ".CREATOR") "MM")
        (field (name ".CHECKED PCB") "RF")
        (field (name ".CHECKED SCH") "RF")
      )
      (libsource (lib "28Pins_Project_V1I1_PCB") (part "RC0805FR-0710KL"))
    )
    (comp (ref "R20")
      (value "10kΩ")
      (footprint "R0805")
      (description "RES SMD 10K OHM 1% 1/8W 0805")
      (fields
        (field (name "MANUFACTURER") "Yageo")
        (field (name "MANUFACTURER PART NUMBER") "RC0805FR-0710KL")
        (field (name ".CREATOR") "MM")
        (field (name ".CHECKED PCB") "RF")
        (field (name ".CHECKED SCH") "RF")
      )
      (libsource (lib "28Pins_Project_V1I1_PCB") (part "RC0805FR-0710KL"))
    )
    (comp (ref "R21")
      (value "10kΩ")
      (footprint "R0805")
      (description "RES SMD 10K OHM 1% 1/8W 0805")
      (fields
        (field (name "MANUFACTURER") "Yageo")
        (field (name "MANUFACTURER PART NUMBER") "RC0805FR-0710KL")
        (field (name ".CREATOR") "MM")
        (field (name ".CHECKED PCB") "RF")
        (field (name ".CHECKED SCH") "RF")
      )
      (libsource (lib "28Pins_Project_V1I1_PCB") (part "RC0805FR-0710KL"))
    )
    (comp (ref "R22")
      (value "560Ω")
      (footprint "R0805")
      (description "RES SMD 560 OHM 1% 1/8W 0805")
      (fields
        (field (name "MANUFACTURER") "Yageo")
        (field (name "MANUFACTURER PART NUMBER") "RC0805FR-07560RL")
        (field (name ".CREATOR") "MM")
        (field (name ".CHECKED PCB") "RF")
        (field (name ".CHECKED SCH") "RF")
      )
      (libsource (lib "28Pins_Project_V1I1_PCB") (part "RC0805FR-07560RL"))
    )
    (comp (ref "R23")
      (value "22Ω")
      (footprint "R0805")
      (description "RES SMD 22 OHM 1% 1/8W 0805")
      (fields
        (field (name "MANUFACTURER") "Yageo")
        (field (name "MANUFACTURER PART NUMBER") "RC0805FR-0722RL")
        (field (name ".CREATOR") "MM")
        (field (name ".CHECKED PCB") "RF")
        (field (name ".CHECKED SCH") "RF")
      )
      (libsource (lib "28Pins_Project_V1I1_PCB") (part "RC0805FR-0722RL"))
    )
    (comp (ref "R24")
      (value "22Ω")
      (footprint "R0805")
      (description "RES SMD 22 OHM 1% 1/8W 0805")
      (fields
        (field (name "MANUFACTURER") "Yageo")
        (field (name "MANUFACTURER PART NUMBER") "RC0805FR-0722RL")
        (field (name ".CREATOR") "MM")
        (field (name ".CHECKED PCB") "RF")
        (field (name ".CHECKED SCH") "RF")
      )
      (libsource (lib "28Pins_Project_V1I1_PCB") (part "RC0805FR-0722RL"))
    )
    (comp (ref "R25")
      (value "22Ω")
      (footprint "R0805")
      (description "RES SMD 22 OHM 1% 1/8W 0805")
      (fields
        (field (name "MANUFACTURER") "Yageo")
        (field (name "MANUFACTURER PART NUMBER") "RC0805FR-0722RL")
        (field (name ".CREATOR") "MM")
        (field (name ".CHECKED PCB") "RF")
        (field (name ".CHECKED SCH") "RF")
      )
      (libsource (lib "28Pins_Project_V1I1_PCB") (part "RC0805FR-0722RL"))
    )
    (comp (ref "R26")
      (value "0Ω")
      (footprint "R0805")
      (description "RES 0.0 OHM 1/8W 0805 SMD")
      (fields
        (field (name "MANUFACTURER") "Yageo")
        (field (name "MANUFACTURER PART NUMBER") "RC0805JR-070RL")
        (field (name ".CHECKED PCB") "RF")
        (field (name ".CHECKED SCH") "RF")
      )
      (libsource (lib "28Pins_Project_V1I1_PCB") (part "RC0805JR-070RL"))
    )
    (comp (ref "R27")
      (value "0Ω")
      (footprint "R0805")
      (description "RES 0.0 OHM 1/8W 0805 SMD")
      (fields
        (field (name "MANUFACTURER") "Yageo")
        (field (name "MANUFACTURER PART NUMBER") "RC0805JR-070RL")
        (field (name ".CHECKED PCB") "RF")
        (field (name ".CHECKED SCH") "RF")
      )
      (libsource (lib "28Pins_Project_V1I1_PCB") (part "RC0805JR-070RL"))
    )
    (comp (ref "R28")
      (value "0Ω")
      (footprint "R0805")
      (description "RES 0.0 OHM 1/8W 0805 SMD")
      (fields
        (field (name "MANUFACTURER") "Yageo")
        (field (name "MANUFACTURER PART NUMBER") "RC0805JR-070RL")
        (field (name ".CHECKED PCB") "RF")
        (field (name ".CHECKED SCH") "RF")
      )
      (libsource (lib "28Pins_Project_V1I1_PCB") (part "RC0805JR-070RL"))
    )
    (comp (ref "SCKT FOR U1")
      (value "4828-3004-CP")
      (footprint "28_DIP_7.62mm_SOCKET")
      (description "CONN IC DIP SOCKET 28POS TIN")
      (fields
        (field (name "MANUFACTURER") "3M")
        (field (name ".CREATOR") "MM")
        (field (name ".CHECKED PCB") "RF")
        (field (name ".CHECKED SCH") "RF")
      )
      (libsource (lib "28Pins_Project_V1I1_PCB") (part "4828-3004-CP"))
    )
    (comp (ref "SW1")
      (value "1825910-6")
      (footprint "1825910-6")
      (description "SWITCH TACTILE SPST-NO 0.05A 24V")
      (fields
        (field (name "MANUFACTURER") "TE Connectivity")
        (field (name ".CREATOR") "MM")
        (field (name ".CHECKED PCB") "RF")
        (field (name ".CHECKED SCH") "RF")
      )
      (libsource (lib "28Pins_Project_V1I1_PCB") (part "1825910-6"))
    )
    (comp (ref "SW2")
      (value "1825910-6")
      (footprint "1825910-6")
      (description "SWITCH TACTILE SPST-NO 0.05A 24V")
      (fields
        (field (name "MANUFACTURER") "TE Connectivity")
        (field (name ".CREATOR") "MM")
        (field (name ".CHECKED PCB") "RF")
        (field (name ".CHECKED SCH") "RF")
      )
      (libsource (lib "28Pins_Project_V1I1_PCB") (part "1825910-6"))
    )
    (comp (ref "U1")
      (value "ATMEGA328P-PU")
      (footprint "28_DIP_7.62mm")
      (description "IC MCU 8BIT 32KB FLASH 28DIP")
      (fields
        (field (name "MANUFACTURER") "Atmel")
        (field (name ".CREATOR") "MM")
        (field (name ".CHECKED PCB") "RF")
        (field (name ".CHECKED SCH") "RF")
      )
      (libsource (lib "28Pins_Project_V1I1_PCB") (part "ATMEGA328P-PU"))
    )
    (comp (ref "U2")
      (value "ATMEGA16U2-AU")
      (footprint "TQFP32")
      (description "IC MCU 8BIT 16KB FLASH 32TQFP")
      (fields
        (field (name "MANUFACTURER") "Atmel")
        (field (name ".CREATOR") "MM")
        (field (name ".CHECKED PCB") "RF")
        (field (name ".CHECKED SCH") "RF")
      )
      (libsource (lib "28Pins_Project_V1I1_PCB") (part "ATMEGA16U2-AU"))
    )
    (comp (ref "U3")
      (value "TL1963A-33DCQR")
      (footprint "DCQ (R-PDSO-G6)")
      (description "IC REG LDO 3.3V 1.5A SOT223-6")
      (fields
        (field (name "MANUFACTURER") "Texas Instruments")
        (field (name ".CREATOR") "MM")
        (field (name ".CHECKED PCB") "RF")
        (field (name ".CHECKED SCH") "RF")
      )
      (libsource (lib "28Pins_Project_V1I1_PCB") (part "TL1963A-33DCQR"))
    )
    (comp (ref "U4")
      (value "SN74AHC1G09DBVR")
      (footprint "DBV_SOT_23_5")
      (description "IC GATE AND SGL 2INP SOT23-5")
      (fields (field (name "MANUFACTURER") "Texas Instruments") (field (name ".CREATOR") "MM"))
      (libsource (lib "28Pins_Project_V1I1_PCB") (part "SN74AHC1G09DBVR"))
    )
    (comp (ref "U5")
      (value "SN74AHC1G09DBVR")
      (footprint "DBV_SOT_23_5")
      (description "IC GATE AND SGL 2INP SOT23-5")
      (fields (field (name "MANUFACTURER") "Texas Instruments") (field (name ".CREATOR") "MM"))
      (libsource (lib "28Pins_Project_V1I1_PCB") (part "SN74AHC1G09DBVR"))
    )
    (comp (ref "U6")
      (value "SN74AHC1G09DBVR")
      (footprint "DBV_SOT_23_5")
      (description "IC GATE AND SGL 2INP SOT23-5")
      (fields (field (name "MANUFACTURER") "Texas Instruments") (field (name ".CREATOR") "MM"))
      (libsource (lib "28Pins_Project_V1I1_PCB") (part "SN74AHC1G09DBVR"))
    )
    (comp (ref "U7")
      (value "SN74AHC1G09DBVR")
      (footprint "DBV_SOT_23_5")
      (description "IC GATE AND SGL 2INP SOT23-5")
      (fields (field (name "MANUFACTURER") "Texas Instruments") (field (name ".CREATOR") "MM"))
      (libsource (lib "28Pins_Project_V1I1_PCB") (part "SN74AHC1G09DBVR"))
    )
    (comp (ref "Y1")
      (value "ABM7-16.000MHZ-D2Y-T")
      (footprint "ABM7_v1_1_BIG")
      (description "CRYSTAL 16MHZ 18PF SMD")
      (fields
        (field (name "MANUFACTURER") "Abracon LLC")
        (field (name ".CREATOR") "MM")
        (field (name ".CHECKED PCB") "RF")
        (field (name ".CHECKED SCH") "RF")
      )
      (libsource (lib "28Pins_Project_V1I1_PCB") (part "ABM7-16.000MHZ-D2Y-T"))
    )
    (comp (ref "Y2")
      (value "ABM7-16.000MHZ-D2Y-T")
      (footprint "ABM7_v1_1_BIG")
      (description "CRYSTAL 16MHZ 18PF SMD")
      (fields
        (field (name "MANUFACTURER") "Abracon LLC")
        (field (name ".CREATOR") "MM")
        (field (name ".CHECKED PCB") "RF")
        (field (name ".CHECKED SCH") "RF")
      )
      (libsource (lib "28Pins_Project_V1I1_PCB") (part "ABM7-16.000MHZ-D2Y-T"))
    )
    (comp (ref "Z1")
      (value "CG0603MLC-05E")
      (footprint "R0603")
      (description "VARISTOR 0603")
      (fields
        (field (name "MANUFACTURER") "Bourns Inc.")
        (field (name ".CREATOR") "MM")
        (field (name ".CHECKED PCB") "RF")
        (field (name ".CHECKED SCH") "RF")
      )
      (libsource (lib "28Pins_Project_V1I1_PCB") (part "CG0603MLC-05E"))
    )
    (comp (ref "Z2")
      (value "CG0603MLC-05E")
      (footprint "R0603")
      (description "VARISTOR 0603")
      (fields
        (field (name "MANUFACTURER") "Bourns Inc.")
        (field (name ".CREATOR") "MM")
        (field (name ".CHECKED PCB") "RF")
        (field (name ".CHECKED SCH") "RF")
      )
      (libsource (lib "28Pins_Project_V1I1_PCB") (part "CG0603MLC-05E"))
    )
  )
  (nets
    (net (code "1") (name "+AREF") (class "Default")
      (node (ref "C21") (pin "1") (pinfunction "1_1") (pintype "passive"))
      (node (ref "C24") (pin "1") (pinfunction "1_1") (pintype "passive"))
      (node (ref "J4") (pin "8") (pinfunction "8_8") (pintype "passive"))
      (node (ref "U1") (pin "21") (pinfunction "AREF_21") (pintype "passive"))
    )
    (net (code "2") (name "/+3V3_16U2_UCAP") (class "Default")
      (node (ref "C7") (pin "2") (pinfunction "2_2") (pintype "passive"))
      (node (ref "R26") (pin "1") (pinfunction "1_1") (pintype "passive"))
      (node (ref "U2") (pin "27") (pinfunction "UCAP_27") (pintype "passive"))
    )
    (net (code "3") (name "/+5V_USB") (class "Default")
      (node (ref "C1") (pin "2") (pinfunction "2_2") (pintype "passive"))
      (node (ref "J7") (pin "1") (pinfunction "P1_1") (pintype "passive"))
      (node (ref "L1") (pin "1") (pinfunction "1_1") (pintype "passive"))
    )
    (net (code "4") (name "/+5V{slash}3V3_16U2") (class "Default")
      (node (ref "C3") (pin "1") (pinfunction "1_1") (pintype "passive"))
      (node (ref "C4") (pin "1") (pinfunction "1_1") (pintype "passive"))
      (node (ref "C5") (pin "1") (pinfunction "1_1") (pintype "passive"))
      (node (ref "FB1") (pin "2") (pinfunction "2_2") (pintype "passive"))
      (node (ref "R26") (pin "2") (pinfunction "2_2") (pintype "passive"))
      (node (ref "U2") (pin "32") (pinfunction "AVCC_32") (pintype "passive"))
      (node (ref "U2") (pin "4") (pinfunction "VCC_4") (pintype "passive"))
    )
    (net (code "5") (name "/+5V{slash}3V3_328P_AVCC") (class "Default")
      (node (ref "C22") (pin "1") (pinfunction "1_1") (pintype "passive"))
      (node (ref "C23") (pin "1") (pinfunction "1_1") (pintype "passive"))
      (node (ref "FB3") (pin "2") (pinfunction "2_2") (pintype "passive"))
      (node (ref "U1") (pin "20") (pinfunction "AVCC_20") (pintype "passive"))
    )
    (net (code "6") (name "/+5V{slash}3V3_328P_VCC") (class "Default")
      (node (ref "C19") (pin "1") (pinfunction "1_1") (pintype "passive"))
      (node (ref "C20") (pin "1") (pinfunction "1_1") (pintype "passive"))
      (node (ref "FB2") (pin "2") (pinfunction "2_2") (pintype "passive"))
      (node (ref "U1") (pin "7") (pinfunction "VCC_7") (pintype "passive"))
    )
    (net (code "7") (name "/16U2PROG_328P_RESETn") (class "Default")
      (node (ref "JP1") (pin "2") (pinfunction "2_2") (pintype "passive"))
      (node (ref "R1") (pin "1") (pinfunction "1_1") (pintype "passive"))
      (node (ref "U2") (pin "13") (pinfunction "(CTS/HWB/AIN6/TO/INT7)PD7_13") (pintype "passive"))
    )
    (net (code "8") (name "/16U2_16MHZ_XTAL1") (class "Default")
      (node (ref "C10") (pin "2") (pinfunction "2_2") (pintype "passive"))
      (node (ref "R9") (pin "1") (pinfunction "1_1") (pintype "passive"))
      (node (ref "U2") (pin "1") (pinfunction "XTAL1_1") (pintype "passive"))
      (node (ref "Y2") (pin "1") (pinfunction "1_1") (pintype "passive"))
    )
    (net (code "9") (name "/16U2_16MHZ_XTAL2") (class "Default")
      (node (ref "C9") (pin "2") (pinfunction "2_2") (pintype "passive"))
      (node (ref "R9") (pin "2") (pinfunction "2_2") (pintype "passive"))
      (node (ref "U2") (pin "2") (pinfunction "XTAL2(PC0)_2") (pintype "passive"))
      (node (ref "Y2") (pin "2") (pinfunction "2_2") (pintype "passive"))
    )
    (net (code "10") (name "/16U2_BUF_RESETn") (class "Default")
      (node (ref "C31") (pin "1") (pinfunction "1_1") (pintype "passive"))
      (node (ref "R23") (pin "2") (pinfunction "2_2") (pintype "passive"))
      (node (ref "U5") (pin "1") (pinfunction "A_1") (pintype "passive"))
      (node (ref "U5") (pin "2") (pinfunction "B_2") (pintype "passive"))
    )
    (net (code "11") (name "/16U2_HDR_RESETn") (class "Default")
      (node (ref "J6") (pin "5") (pinfunction "5_5") (pintype "passive"))
      (node (ref "JP3") (pin "3") (pinfunction "3_3") (pintype "passive"))
    )
    (net (code "12") (name "/16U2_MISO") (class "Default")
      (node (ref "J6") (pin "1") (pinfunction "1_1") (pintype "passive"))
      (node (ref "U2") (pin "17") (pinfunction "(PD0/MISO/PCINT3)PB3_17") (pintype "passive"))
    )
    (net (code "13") (name "/16U2_PB4") (class "Default")
      (node (ref "JP2") (pin "1") (pinfunction "1_1") (pintype "passive"))
      (node (ref "JP3") (pin "2") (pinfunction "2_2") (pintype "passive"))
      (node (ref "U2") (pin "18") (pinfunction "(T1/PCINT4)PB4_18") (pintype "passive"))
    )
    (net (code "14") (name "/16U2_PB5") (class "Default")
      (node (ref "JP2") (pin "3") (pinfunction "3_3") (pintype "passive"))
      (node (ref "U2") (pin "19") (pinfunction "(PCINT5)PB5_19") (pintype "passive"))
    )
    (net (code "15") (name "/16U2_PB6") (class "Default")
      (node (ref "JP2") (pin "2") (pinfunction "2_2") (pintype "passive"))
      (node (ref "U2") (pin "20") (pinfunction "(PCINT6)PB6_20") (pintype "passive"))
    )
    (net (code "16") (name "/16U2_PB7") (class "Default")
      (node (ref "JP2") (pin "4") (pinfunction "4_4") (pintype "passive"))
      (node (ref "U2") (pin "21") (pinfunction "(PCINT7/OC0A/OC1C)PB7_21") (pintype "passive"))
    )
    (net (code "17") (name "/16U2_RESETn") (class "Default")
      (node (ref "JP3") (pin "4") (pinfunction "4_4") (pintype "passive"))
      (node (ref "R4") (pin "1") (pinfunction "1_1") (pintype "passive"))
      (node (ref "U2") (pin "24") (pinfunction "RESET(PC1/DW)_24") (pintype "passive"))
      (node (ref "U5") (pin "4") (pinfunction "Y_4") (pintype "passive"))
    )
    (net (code "18") (name "/16U2_RXD") (class "Default")
      (node (ref "R11") (pin "1") (pinfunction "1_1") (pintype "passive"))
      (node (ref "U2") (pin "8") (pinfunction "(RXD1/AIN1/INT2)PD2_8") (pintype "passive"))
    )
    (net (code "19") (name "/16U2_RX_LED") (class "Default")
      (node (ref "D4") (pin "1") (pinfunction "cathode_1") (pintype "passive"))
      (node (ref "U2") (pin "10") (pinfunction "(INT5/AIN3)PD4_10") (pintype "passive"))
    )
    (net (code "20") (name "/16U2_SCLK") (class "Default")
      (node (ref "J6") (pin "3") (pinfunction "3_3") (pintype "passive"))
      (node (ref "R5") (pin "2") (pinfunction "2_2") (pintype "passive"))
    )
    (net (code "21") (name "/16U2_SCLK_R") (class "Default")
      (node (ref "R5") (pin "1") (pinfunction "1_1") (pintype "passive"))
      (node (ref "U2") (pin "15") (pinfunction "(SCLK/PCINT1)PB1_15") (pintype "passive"))
    )
    (net (code "22") (name "/16U2_TXD") (class "Default")
      (node (ref "R10") (pin "1") (pinfunction "1_1") (pintype "passive"))
      (node (ref "U2") (pin "9") (pinfunction "(TXD1/INT3)PD3_9") (pintype "passive"))
    )
    (net (code "23") (name "/16U2_TX_LED") (class "Default")
      (node (ref "D3") (pin "1") (pinfunction "cathode_1") (pintype "passive"))
      (node (ref "U2") (pin "11") (pinfunction "(XCK/AIN4/PCINT12)PD5_11") (pintype "passive"))
    )
    (net (code "24") (name "/328P_16MHZ_XTAL1") (class "Default")
      (node (ref "C27") (pin "2") (pinfunction "2_2") (pintype "passive"))
      (node (ref "R16") (pin "1") (pinfunction "1_1") (pintype "passive"))
      (node (ref "U1") (pin "9") (pinfunction "XTAL1_9") (pintype "passive"))
      (node (ref "Y1") (pin "1") (pinfunction "1_1") (pintype "passive"))
    )
    (net (code "25") (name "/328P_16MHZ_XTAL2") (class "Default")
      (node (ref "C25") (pin "2") (pinfunction "2_2") (pintype "passive"))
      (node (ref "R16") (pin "2") (pinfunction "2_2") (pintype "passive"))
      (node (ref "U1") (pin "10") (pinfunction "XTAL2_10") (pintype "passive"))
      (node (ref "Y1") (pin "2") (pinfunction "2_2") (pintype "passive"))
    )
    (net (code "26") (name "/328P_AUTORESETn") (class "Default")
      (node (ref "C11") (pin "1") (pinfunction "1_1") (pintype "passive"))
      (node (ref "R18") (pin "1") (pinfunction "1_1") (pintype "passive"))
      (node (ref "U6") (pin "1") (pinfunction "A_1") (pintype "passive"))
    )
    (net (code "27") (name "/328P_BUF_RESETn") (class "Default")
      (node (ref "C32") (pin "1") (pinfunction "1_1") (pintype "passive"))
      (node (ref "R24") (pin "2") (pinfunction "2_2") (pintype "passive"))
      (node (ref "U6") (pin "2") (pinfunction "B_2") (pintype "passive"))
    )
    (net (code "28") (name "/328P_RESETn") (class "Default")
      (node (ref "J1") (pin "3") (pinfunction "3_3") (pintype "passive"))
      (node (ref "J5") (pin "5") (pinfunction "5_5") (pintype "passive"))
      (node (ref "JP3") (pin "1") (pinfunction "1_1") (pintype "passive"))
      (node (ref "R14") (pin "1") (pinfunction "1_1") (pintype "passive"))
      (node (ref "U1") (pin "1") (pinfunction "RESET_1") (pintype "passive"))
      (node (ref "U6") (pin "4") (pinfunction "Y_4") (pintype "passive"))
    )
    (net (code "29") (name "/AD0") (class "Default")
      (node (ref "J2") (pin "1") (pinfunction "1_1") (pintype "passive"))
      (node (ref "U1") (pin "23") (pinfunction "(ADC0)PC0)_23") (pintype "passive"))
    )
    (net (code "30") (name "/AD1") (class "Default")
      (node (ref "J2") (pin "2") (pinfunction "2_2") (pintype "passive"))
      (node (ref "U1") (pin "24") (pinfunction "(ADC1)PC1_24") (pintype "passive"))
    )
    (net (code "31") (name "/AD2") (class "Default")
      (node (ref "J2") (pin "3") (pinfunction "3_3") (pintype "passive"))
      (node (ref "U1") (pin "25") (pinfunction "(ADC2)PC2_25") (pintype "passive"))
    )
    (net (code "32") (name "/AD3") (class "Default")
      (node (ref "J2") (pin "4") (pinfunction "4_4") (pintype "passive"))
      (node (ref "U1") (pin "26") (pinfunction "(ADC3)PC3_26") (pintype "passive"))
    )
    (net (code "33") (name "/AD4{slash}SDA") (class "Default")
      (node (ref "J2") (pin "5") (pinfunction "5_5") (pintype "passive"))
      (node (ref "J4") (pin "9") (pinfunction "9_9") (pintype "passive"))
      (node (ref "U1") (pin "27") (pinfunction "(ADC4)PC4_27") (pintype "passive"))
    )
    (net (code "34") (name "/AD5{slash}SCL") (class "Default")
      (node (ref "J2") (pin "6") (pinfunction "6_6") (pintype "passive"))
      (node (ref "J4") (pin "10") (pinfunction "10_10") (pintype "passive"))
      (node (ref "U1") (pin "28") (pinfunction "(ADC5)PC5_28") (pintype "passive"))
    )
    (net (code "35") (name "/BUTTON_RESETn") (class "Default")
      (node (ref "D6") (pin "2") (pinfunction "Anode_2") (pintype "passive"))
      (node (ref "R20") (pin "1") (pinfunction "1_1") (pintype "passive"))
      (node (ref "R24") (pin "1") (pinfunction "1_1") (pintype "passive"))
      (node (ref "SW1") (pin "1") (pinfunction "1_1") (pintype "passive"))
      (node (ref "SW1") (pin "2") (pinfunction "2_2") (pintype "passive"))
    )
    (net (code "36") (name "/CON_USB_N") (class "Default")
      (node (ref "J7") (pin "2") (pinfunction "P2_2") (pintype "passive"))
      (node (ref "R6") (pin "1") (pinfunction "1_1") (pintype "passive"))
      (node (ref "Z1") (pin "2") (pinfunction "2_2") (pintype "passive"))
    )
    (net (code "37") (name "/CON_USB_P") (class "Default")
      (node (ref "J7") (pin "3") (pinfunction "P3_3") (pintype "passive"))
      (node (ref "R7") (pin "1") (pinfunction "1_1") (pintype "passive"))
      (node (ref "Z2") (pin "2") (pinfunction "2_2") (pintype "passive"))
    )
    (net (code "38") (name "/IO0") (class "Default")
      (node (ref "J3") (pin "1") (pinfunction "1_1") (pintype "passive"))
      (node (ref "R10") (pin "2") (pinfunction "2_2") (pintype "passive"))
      (node (ref "U1") (pin "2") (pinfunction "(RXD)PD0_2") (pintype "passive"))
    )
    (net (code "39") (name "/IO1") (class "Default")
      (node (ref "J3") (pin "2") (pinfunction "2_2") (pintype "passive"))
      (node (ref "R11") (pin "2") (pinfunction "2_2") (pintype "passive"))
      (node (ref "U1") (pin "3") (pinfunction "(TXD)PD1_3") (pintype "passive"))
    )
    (net (code "40") (name "/IO2") (class "Default")
      (node (ref "J3") (pin "3") (pinfunction "3_3") (pintype "passive"))
      (node (ref "U1") (pin "4") (pinfunction "(INT0)PD2_4") (pintype "passive"))
    )
    (net (code "41") (name "/IO3") (class "Default")
      (node (ref "J3") (pin "4") (pinfunction "4_4") (pintype "passive"))
      (node (ref "U1") (pin "5") (pinfunction "(INT1)PD3_5") (pintype "passive"))
    )
    (net (code "42") (name "/IO4") (class "Default")
      (node (ref "J3") (pin "5") (pinfunction "5_5") (pintype "passive"))
      (node (ref "U1") (pin "6") (pinfunction "(T0)PD4_6") (pintype "passive"))
    )
    (net (code "43") (name "/IO5") (class "Default")
      (node (ref "J3") (pin "6") (pinfunction "6_6") (pintype "passive"))
      (node (ref "U1") (pin "11") (pinfunction "(T1)PD5_11") (pintype "passive"))
    )
    (net (code "44") (name "/IO6") (class "Default")
      (node (ref "J3") (pin "7") (pinfunction "7_7") (pintype "passive"))
      (node (ref "U1") (pin "12") (pinfunction "(AIN0)PD6_12") (pintype "passive"))
    )
    (net (code "45") (name "/IO7") (class "Default")
      (node (ref "J3") (pin "8") (pinfunction "8_8") (pintype "passive"))
      (node (ref "U1") (pin "13") (pinfunction "(AIN1)PD7_13") (pintype "passive"))
    )
    (net (code "46") (name "/IO8") (class "Default")
      (node (ref "J4") (pin "1") (pinfunction "1_1") (pintype "passive"))
      (node (ref "R22") (pin "1") (pinfunction "1_1") (pintype "passive"))
      (node (ref "U1") (pin "14") (pinfunction "(ICP)PB0_14") (pintype "passive"))
    )
    (net (code "47") (name "/IO9") (class "Default")
      (node (ref "J4") (pin "2") (pinfunction "2_2") (pintype "passive"))
      (node (ref "U1") (pin "15") (pinfunction "(OC1)PB1_15") (pintype "passive"))
    )
    (net (code "48") (name "/MISO") (class "Default")
      (node (ref "J4") (pin "5") (pinfunction "5_5") (pintype "passive"))
      (node (ref "J5") (pin "1") (pinfunction "1_1") (pintype "passive"))
      (node (ref "U1") (pin "18") (pinfunction "(MISO)PB4_18") (pintype "passive"))
    )
    (net (code "49") (name "/MOSI") (class "Default")
      (node (ref "J4") (pin "4") (pinfunction "4_4") (pintype "passive"))
      (node (ref "J5") (pin "4") (pinfunction "4_4") (pintype "passive"))
      (node (ref "U1") (pin "17") (pinfunction "(MOSI)PB3_17") (pintype "passive"))
    )
    (net (code "50") (name "/SCK") (class "Default")
      (node (ref "J4") (pin "6") (pinfunction "6_6") (pintype "passive"))
      (node (ref "J5") (pin "3") (pinfunction "3_3") (pintype "passive"))
      (node (ref "R13") (pin "2") (pinfunction "2_2") (pintype "passive"))
      (node (ref "U4") (pin "1") (pinfunction "A_1") (pintype "passive"))
      (node (ref "U4") (pin "2") (pinfunction "B_2") (pintype "passive"))
    )
    (net (code "51") (name "/SCK_R") (class "Default")
      (node (ref "R13") (pin "1") (pinfunction "1_1") (pintype "passive"))
      (node (ref "U1") (pin "19") (pinfunction "(SCK)PB5_19") (pintype "passive"))
    )
    (net (code "52") (name "/SS") (class "Default")
      (node (ref "J4") (pin "3") (pinfunction "3_3") (pintype "passive"))
      (node (ref "U1") (pin "16") (pinfunction "(SS)PB2_16") (pintype "passive"))
    )
    (net (code "53") (name "/USB_N") (class "Default")
      (node (ref "R6") (pin "2") (pinfunction "2_2") (pintype "passive"))
      (node (ref "U2") (pin "30") (pinfunction "D-_30") (pintype "passive"))
    )
    (net (code "54") (name "/USB_P") (class "Default")
      (node (ref "R7") (pin "2") (pinfunction "2_2") (pintype "passive"))
      (node (ref "U2") (pin "29") (pinfunction "D+_29") (pintype "passive"))
    )
    (net (code "55") (name "/USER_BUTTON") (class "Default")
      (node (ref "R21") (pin "1") (pinfunction "1_1") (pintype "passive"))
      (node (ref "R25") (pin "1") (pinfunction "1_1") (pintype "passive"))
      (node (ref "SW2") (pin "1") (pinfunction "1_1") (pintype "passive"))
      (node (ref "SW2") (pin "2") (pinfunction "2_2") (pintype "passive"))
    )
    (net (code "56") (name "/USER_BUTTON_BUF") (class "Default")
      (node (ref "C33") (pin "1") (pinfunction "1_1") (pintype "passive"))
      (node (ref "R25") (pin "2") (pinfunction "2_2") (pintype "passive"))
      (node (ref "U7") (pin "1") (pinfunction "A_1") (pintype "passive"))
      (node (ref "U7") (pin "2") (pinfunction "B_2") (pintype "passive"))
    )
    (net (code "57") (name "3V3") (class "Default")
      (node (ref "C13") (pin "1") (pinfunction "1_1") (pintype "passive"))
      (node (ref "C16") (pin "1") (pinfunction "1_1") (pintype "passive"))
      (node (ref "J1") (pin "4") (pinfunction "4_4") (pintype "passive"))
      (node (ref "JP4") (pin "3") (pinfunction "3_3") (pintype "passive"))
      (node (ref "R28") (pin "1") (pinfunction "1_1") (pintype "passive"))
      (node (ref "U3") (pin "4") (pinfunction "OUT_4") (pintype "passive"))
    )
    (net (code "58") (name "5V0") (class "Default")
      (node (ref "C12") (pin "1") (pinfunction "1_1") (pintype "passive"))
      (node (ref "C14") (pin "1") (pinfunction "1_1") (pintype "passive"))
      (node (ref "C2") (pin "2") (pinfunction "2_2") (pintype "passive"))
      (node (ref "C6") (pin "1") (pinfunction "1_1") (pintype "passive"))
      (node (ref "J1") (pin "5") (pinfunction "5_5") (pintype "passive"))
      (node (ref "J8") (pin "1") (pinfunction "1_1") (pintype "passive"))
      (node (ref "JP4") (pin "1") (pinfunction "1_1") (pintype "passive"))
      (node (ref "L1") (pin "2") (pinfunction "2_2") (pintype "passive"))
      (node (ref "R27") (pin "2") (pinfunction "2_2") (pintype "passive"))
      (node (ref "U2") (pin "31") (pinfunction "UVCC_31") (pintype "passive"))
      (node (ref "U3") (pin "1") (pinfunction "~{SHDN}_1") (pintype "passive"))
      (node (ref "U3") (pin "2") (pinfunction "IN_2") (pintype "passive"))
    )
    (net (code "59") (name "5V0{slash}3V3") (class "Default")
      (node (ref "C15") (pin "1") (pinfunction "1_1") (pintype "passive"))
      (node (ref "C17") (pin "1") (pinfunction "1_1") (pintype "passive"))
      (node (ref "C26") (pin "1") (pinfunction "1_1") (pintype "passive"))
      (node (ref "C28") (pin "1") (pinfunction "1_1") (pintype "passive"))
      (node (ref "C29") (pin "1") (pinfunction "1_1") (pintype "passive"))
      (node (ref "C30") (pin "1") (pinfunction "1_1") (pintype "passive"))
      (node (ref "C34") (pin "1") (pinfunction "1_1") (pintype "passive"))
      (node (ref "C8") (pin "1") (pinfunction "1_1") (pintype "passive"))
      (node (ref "D5") (pin "1") (pinfunction "Cathode_1") (pintype "passive"))
      (node (ref "D6") (pin "1") (pinfunction "Cathode_1") (pintype "passive"))
      (node (ref "FB1") (pin "1") (pinfunction "1_1") (pintype "passive"))
      (node (ref "FB2") (pin "1") (pinfunction "1_1") (pintype "passive"))
      (node (ref "FB3") (pin "1") (pinfunction "1_1") (pintype "passive"))
      (node (ref "J1") (pin "2") (pinfunction "2_2") (pintype "passive"))
      (node (ref "J5") (pin "2") (pinfunction "2_2") (pintype "passive"))
      (node (ref "J6") (pin "2") (pinfunction "2_2") (pintype "passive"))
      (node (ref "J6") (pin "4") (pinfunction "4_4") (pintype "passive"))
      (node (ref "JP4") (pin "2") (pinfunction "2_2") (pintype "passive"))
      (node (ref "R1") (pin "2") (pinfunction "2_2") (pintype "passive"))
      (node (ref "R14") (pin "2") (pinfunction "2_2") (pintype "passive"))
      (node (ref "R15") (pin "2") (pinfunction "2_2") (pintype "passive"))
      (node (ref "R17") (pin "2") (pinfunction "2_2") (pintype "passive"))
      (node (ref "R18") (pin "2") (pinfunction "2_2") (pintype "passive"))
      (node (ref "R19") (pin "2") (pinfunction "2_2") (pintype "passive"))
      (node (ref "R2") (pin "2") (pinfunction "2_2") (pintype "passive"))
      (node (ref "R20") (pin "2") (pinfunction "2_2") (pintype "passive"))
      (node (ref "R21") (pin "2") (pinfunction "2_2") (pintype "passive"))
      (node (ref "R27") (pin "1") (pinfunction "1_1") (pintype "passive"))
      (node (ref "R28") (pin "2") (pinfunction "2_2") (pintype "passive"))
      (node (ref "R3") (pin "2") (pinfunction "2_2") (pintype "passive"))
      (node (ref "R4") (pin "2") (pinfunction "2_2") (pintype "passive"))
      (node (ref "U2") (pin "16") (pinfunction "(PDI/MOSI/PCINT2)PB2_16") (pintype "passive"))
      (node (ref "U4") (pin "5") (pinfunction "VCC_5") (pintype "power_in"))
      (node (ref "U5") (pin "5") (pinfunction "VCC_5") (pintype "power_in"))
      (node (ref "U6") (pin "5") (pinfunction "VCC_5") (pintype "power_in"))
      (node (ref "U7") (pin "5") (pinfunction "VCC_5") (pintype "power_in"))
    )
    (net (code "60") (name "GND") (class "Default")
      (node (ref "C1") (pin "1") (pinfunction "1_1") (pintype "passive"))
      (node (ref "C10") (pin "1") (pinfunction "1_1") (pintype "passive"))
      (node (ref "C12") (pin "2") (pinfunction "2_2") (pintype "passive"))
      (node (ref "C13") (pin "2") (pinfunction "2_2") (pintype "passive"))
      (node (ref "C14") (pin "2") (pinfunction "2_2") (pintype "passive"))
      (node (ref "C15") (pin "2") (pinfunction "2_2") (pintype "passive"))
      (node (ref "C16") (pin "2") (pinfunction "2_2") (pintype "passive"))
      (node (ref "C17") (pin "2") (pinfunction "2_2") (pintype "passive"))
      (node (ref "C19") (pin "2") (pinfunction "2_2") (pintype "passive"))
      (node (ref "C2") (pin "1") (pinfunction "1_1") (pintype "passive"))
      (node (ref "C20") (pin "2") (pinfunction "2_2") (pintype "passive"))
      (node (ref "C21") (pin "2") (pinfunction "2_2") (pintype "passive"))
      (node (ref "C22") (pin "2") (pinfunction "2_2") (pintype "passive"))
      (node (ref "C23") (pin "2") (pinfunction "2_2") (pintype "passive"))
      (node (ref "C24") (pin "2") (pinfunction "2_2") (pintype "passive"))
      (node (ref "C25") (pin "1") (pinfunction "1_1") (pintype "passive"))
      (node (ref "C26") (pin "2") (pinfunction "2_2") (pintype "passive"))
      (node (ref "C27") (pin "1") (pinfunction "1_1") (pintype "passive"))
      (node (ref "C28") (pin "2") (pinfunction "2_2") (pintype "passive"))
      (node (ref "C29") (pin "2") (pinfunction "2_2") (pintype "passive"))
      (node (ref "C3") (pin "2") (pinfunction "2_2") (pintype "passive"))
      (node (ref "C30") (pin "2") (pinfunction "2_2") (pintype "passive"))
      (node (ref "C31") (pin "2") (pinfunction "2_2") (pintype "passive"))
      (node (ref "C32") (pin "2") (pinfunction "2_2") (pintype "passive"))
      (node (ref "C33") (pin "2") (pinfunction "2_2") (pintype "passive"))
      (node (ref "C34") (pin "2") (pinfunction "2_2") (pintype "passive"))
      (node (ref "C4") (pin "2") (pinfunction "2_2") (pintype "passive"))
      (node (ref "C5") (pin "2") (pinfunction "2_2") (pintype "passive"))
      (node (ref "C6") (pin "2") (pinfunction "2_2") (pintype "passive"))
      (node (ref "C7") (pin "1") (pinfunction "1_1") (pintype "passive"))
      (node (ref "C8") (pin "2") (pinfunction "2_2") (pintype "passive"))
      (node (ref "C9") (pin "1") (pinfunction "1_1") (pintype "passive"))
      (node (ref "D1") (pin "1") (pinfunction "cathode_1") (pintype "passive"))
      (node (ref "J1") (pin "6") (pinfunction "6_6") (pintype "passive"))
      (node (ref "J1") (pin "7") (pinfunction "7_7") (pintype "passive"))
      (node (ref "J4") (pin "7") (pinfunction "7_7") (pintype "passive"))
      (node (ref "J5") (pin "6") (pinfunction "6_6") (pintype "passive"))
      (node (ref "J6") (pin "6") (pinfunction "6_6") (pintype "passive"))
      (node (ref "J7") (pin "10") (pinfunction "10_10") (pintype "passive"))
      (node (ref "J7") (pin "11") (pinfunction "11_11") (pintype "passive"))
      (node (ref "J7") (pin "5") (pinfunction "P5_5") (pintype "passive"))
      (node (ref "J7") (pin "6") (pinfunction "6_6") (pintype "passive"))
      (node (ref "J7") (pin "7") (pinfunction "7_7") (pintype "passive"))
      (node (ref "J7") (pin "8") (pinfunction "8_8") (pintype "passive"))
      (node (ref "J7") (pin "9") (pinfunction "9_9") (pintype "passive"))
      (node (ref "J9") (pin "1") (pinfunction "1_1") (pintype "passive"))
      (node (ref "MH1") (pin "1") (pinfunction "1_1") (pintype "passive"))
      (node (ref "MH2") (pin "1") (pinfunction "1_1") (pintype "passive"))
      (node (ref "MH3") (pin "1") (pinfunction "1_1") (pintype "passive"))
      (node (ref "R12") (pin "2") (pinfunction "2_2") (pintype "passive"))
      (node (ref "R8") (pin "2") (pinfunction "2_2") (pintype "passive"))
      (node (ref "SW1") (pin "3") (pinfunction "MECH1_3") (pintype "passive"))
      (node (ref "SW1") (pin "4") (pinfunction "MECH2_4") (pintype "passive"))
      (node (ref "SW2") (pin "3") (pinfunction "MECH1_3") (pintype "passive"))
      (node (ref "SW2") (pin "4") (pinfunction "MECH2_4") (pintype "passive"))
      (node (ref "U1") (pin "22") (pinfunction "AGND_22") (pintype "passive"))
      (node (ref "U1") (pin "8") (pinfunction "GND_8") (pintype "passive"))
      (node (ref "U2") (pin "28") (pinfunction "UGND_28") (pintype "passive"))
      (node (ref "U2") (pin "3") (pinfunction "GND_3") (pintype "passive"))
      (node (ref "U3") (pin "3") (pinfunction "GND_3") (pintype "passive"))
      (node (ref "U3") (pin "6") (pinfunction "EPAD_6") (pintype "passive"))
      (node (ref "U4") (pin "3") (pinfunction "GND_3") (pintype "power_in"))
      (node (ref "U5") (pin "3") (pinfunction "GND_3") (pintype "power_in"))
      (node (ref "U6") (pin "3") (pinfunction "GND_3") (pintype "power_in"))
      (node (ref "U7") (pin "3") (pinfunction "GND_3") (pintype "power_in"))
      (node (ref "Z1") (pin "1") (pinfunction "1_1") (pintype "passive"))
      (node (ref "Z2") (pin "1") (pinfunction "1_1") (pintype "passive"))
    )
    (net (code "61") (name "Net-(C11-Pad2)") (class "Default")
      (node (ref "C11") (pin "2") (pinfunction "2_2") (pintype "passive"))
      (node (ref "JP1") (pin "1") (pinfunction "1_1") (pintype "passive"))
    )
    (net (code "62") (name "Net-(D1-ANODE)") (class "Default")
      (node (ref "D1") (pin "2") (pinfunction "ANODE_2") (pintype "passive"))
      (node (ref "R17") (pin "1") (pinfunction "1_1") (pintype "passive"))
    )
    (net (code "63") (name "Net-(D2-ANODE)") (class "Default")
      (node (ref "D2") (pin "2") (pinfunction "ANODE_2") (pintype "passive"))
      (node (ref "R15") (pin "1") (pinfunction "1_1") (pintype "passive"))
    )
    (net (code "64") (name "Net-(D2-cathode)") (class "Default")
      (node (ref "D2") (pin "1") (pinfunction "cathode_1") (pintype "passive"))
      (node (ref "U4") (pin "4") (pinfunction "Y_4") (pintype "passive"))
    )
    (net (code "65") (name "Net-(D3-ANODE)") (class "Default")
      (node (ref "D3") (pin "2") (pinfunction "ANODE_2") (pintype "passive"))
      (node (ref "R2") (pin "1") (pinfunction "1_1") (pintype "passive"))
    )
    (net (code "66") (name "Net-(D4-ANODE)") (class "Default")
      (node (ref "D4") (pin "2") (pinfunction "ANODE_2") (pintype "passive"))
      (node (ref "R3") (pin "1") (pinfunction "1_1") (pintype "passive"))
    )
    (net (code "67") (name "Net-(D5-Anode)") (class "Default")
      (node (ref "D5") (pin "2") (pinfunction "Anode_2") (pintype "passive"))
      (node (ref "R19") (pin "1") (pinfunction "1_1") (pintype "passive"))
      (node (ref "R23") (pin "1") (pinfunction "1_1") (pintype "passive"))
    )
    (net (code "68") (name "Net-(J7-P4)") (class "Default")
      (node (ref "J7") (pin "4") (pinfunction "P4_4") (pintype "passive"))
      (node (ref "R8") (pin "1") (pinfunction "1_1") (pintype "passive"))
    )
    (net (code "69") (name "Net-(JP1-Pad3)") (class "Default")
      (node (ref "JP1") (pin "3") (pinfunction "3_3") (pintype "passive"))
      (node (ref "R12") (pin "1") (pinfunction "1_1") (pintype "passive"))
    )
    (net (code "70") (name "Net-(U7-Y)") (class "Default")
      (node (ref "R22") (pin "2") (pinfunction "2_2") (pintype "passive"))
      (node (ref "U7") (pin "4") (pinfunction "Y_4") (pintype "passive"))
    )
    (net (code "71") (name "unconnected-(J1-Pad1)") (class "Default")
      (node (ref "J1") (pin "1") (pinfunction "1_1") (pintype "passive+no_connect"))
    )
    (net (code "72") (name "unconnected-(J1-Pad8)") (class "Default")
      (node (ref "J1") (pin "8") (pinfunction "8_8") (pintype "passive+no_connect"))
    )
    (net (code "73") (name "unconnected-(MH4-Pad1)") (class "Default")
      (node (ref "MH4") (pin "1") (pinfunction "1_1") (pintype "passive+no_connect"))
    )
    (net (code "74") (name "unconnected-(U2-(AIN0{slash}INT1)PD1-Pad7)") (class "Default")
      (node (ref "U2") (pin "7") (pinfunction "(AIN0/INT1)PD1_7") (pintype "passive+no_connect"))
    )
    (net (code "75") (name "unconnected-(U2-(AIN2{slash}PCINT11)PC2-Pad5)") (class "Default")
      (node (ref "U2") (pin "5") (pinfunction "(AIN2/PCINT11)PC2_5") (pintype "passive+no_connect"))
    )
    (net (code "76") (name "unconnected-(U2-(INT4{slash}ICP1{slash}CLK0)PC7-Pad22)") (class "Default")
      (node (ref "U2") (pin "22") (pinfunction "(INT4/ICP1/CLK0)PC7_22") (pintype "passive+no_connect"))
    )
    (net (code "77") (name "unconnected-(U2-(OC0B{slash}INT0)PD0-Pad6)") (class "Default")
      (node (ref "U2") (pin "6") (pinfunction "(OC0B/INT0)PD0_6") (pintype "passive+no_connect"))
    )
    (net (code "78") (name "unconnected-(U2-(OC1A{slash}PCINT8)PC6-Pad23)") (class "Default")
      (node (ref "U2") (pin "23") (pinfunction "(OC1A/PCINT8)PC6_23") (pintype "passive+no_connect"))
    )
    (net (code "79") (name "unconnected-(U2-(PCINT9{slash}OC1B)PC5-Pad25)") (class "Default")
      (node (ref "U2") (pin "25") (pinfunction "(PCINT9/OC1B)PC5_25") (pintype "passive+no_connect"))
    )
    (net (code "80") (name "unconnected-(U2-(PCINT10)PC4-Pad26)") (class "Default")
      (node (ref "U2") (pin "26") (pinfunction "(PCINT10)PC4_26") (pintype "passive+no_connect"))
    )
    (net (code "81") (name "unconnected-(U2-(RTS{slash}AIN5{slash}INT6)PD6-Pad12)") (class "Default")
      (node (ref "U2") (pin "12") (pinfunction "(RTS/AIN5/INT6)PD6_12") (pintype "passive"))
    )
    (net (code "82") (name "unconnected-(U2-(SS{slash}PCINT0)PB0-Pad14)") (class "Default")
      (node (ref "U2") (pin "14") (pinfunction "(SS/PCINT0)PB0_14") (pintype "passive+no_connect"))
    )
    (net (code "83") (name "unconnected-(U3-SENSE-Pad5)") (class "Default")
      (node (ref "U3") (pin "5") (pinfunction "SENSE_5") (pintype "passive"))
    )
  )
)
